# Overview_Schematic.net
KiCad netlist of a schematic drawn in EAGLE
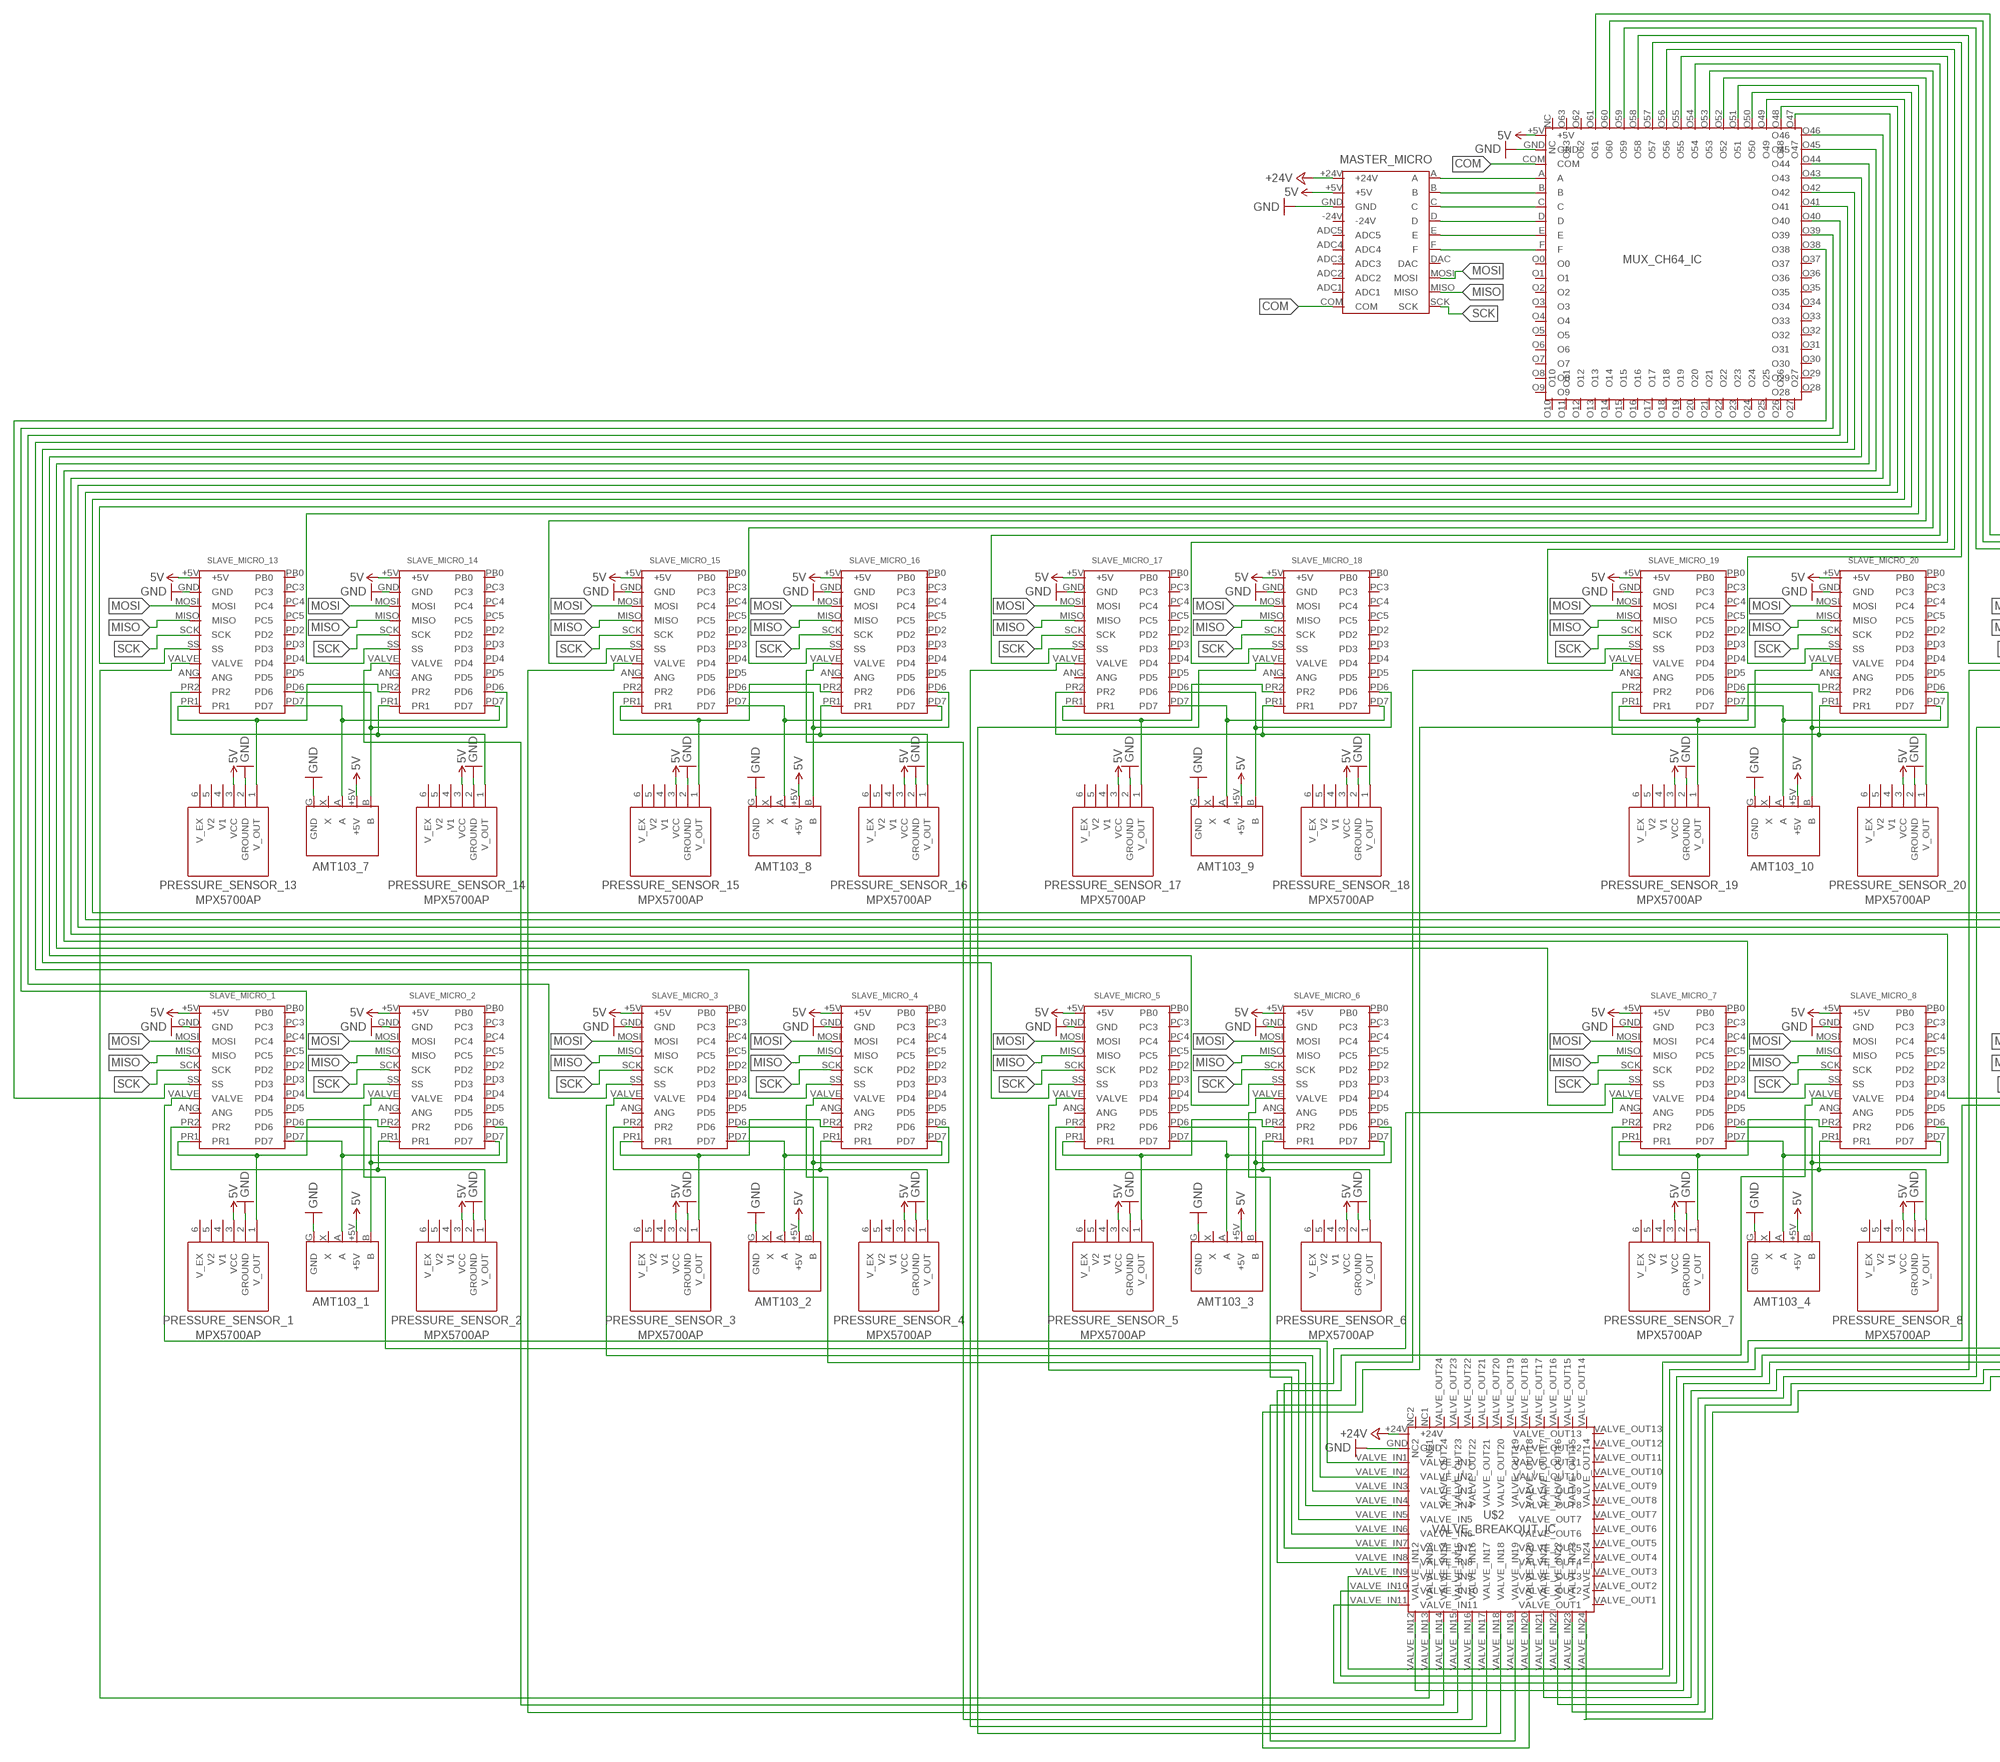
[diagram p0: schematic, sheet 1, part 1 of 2]
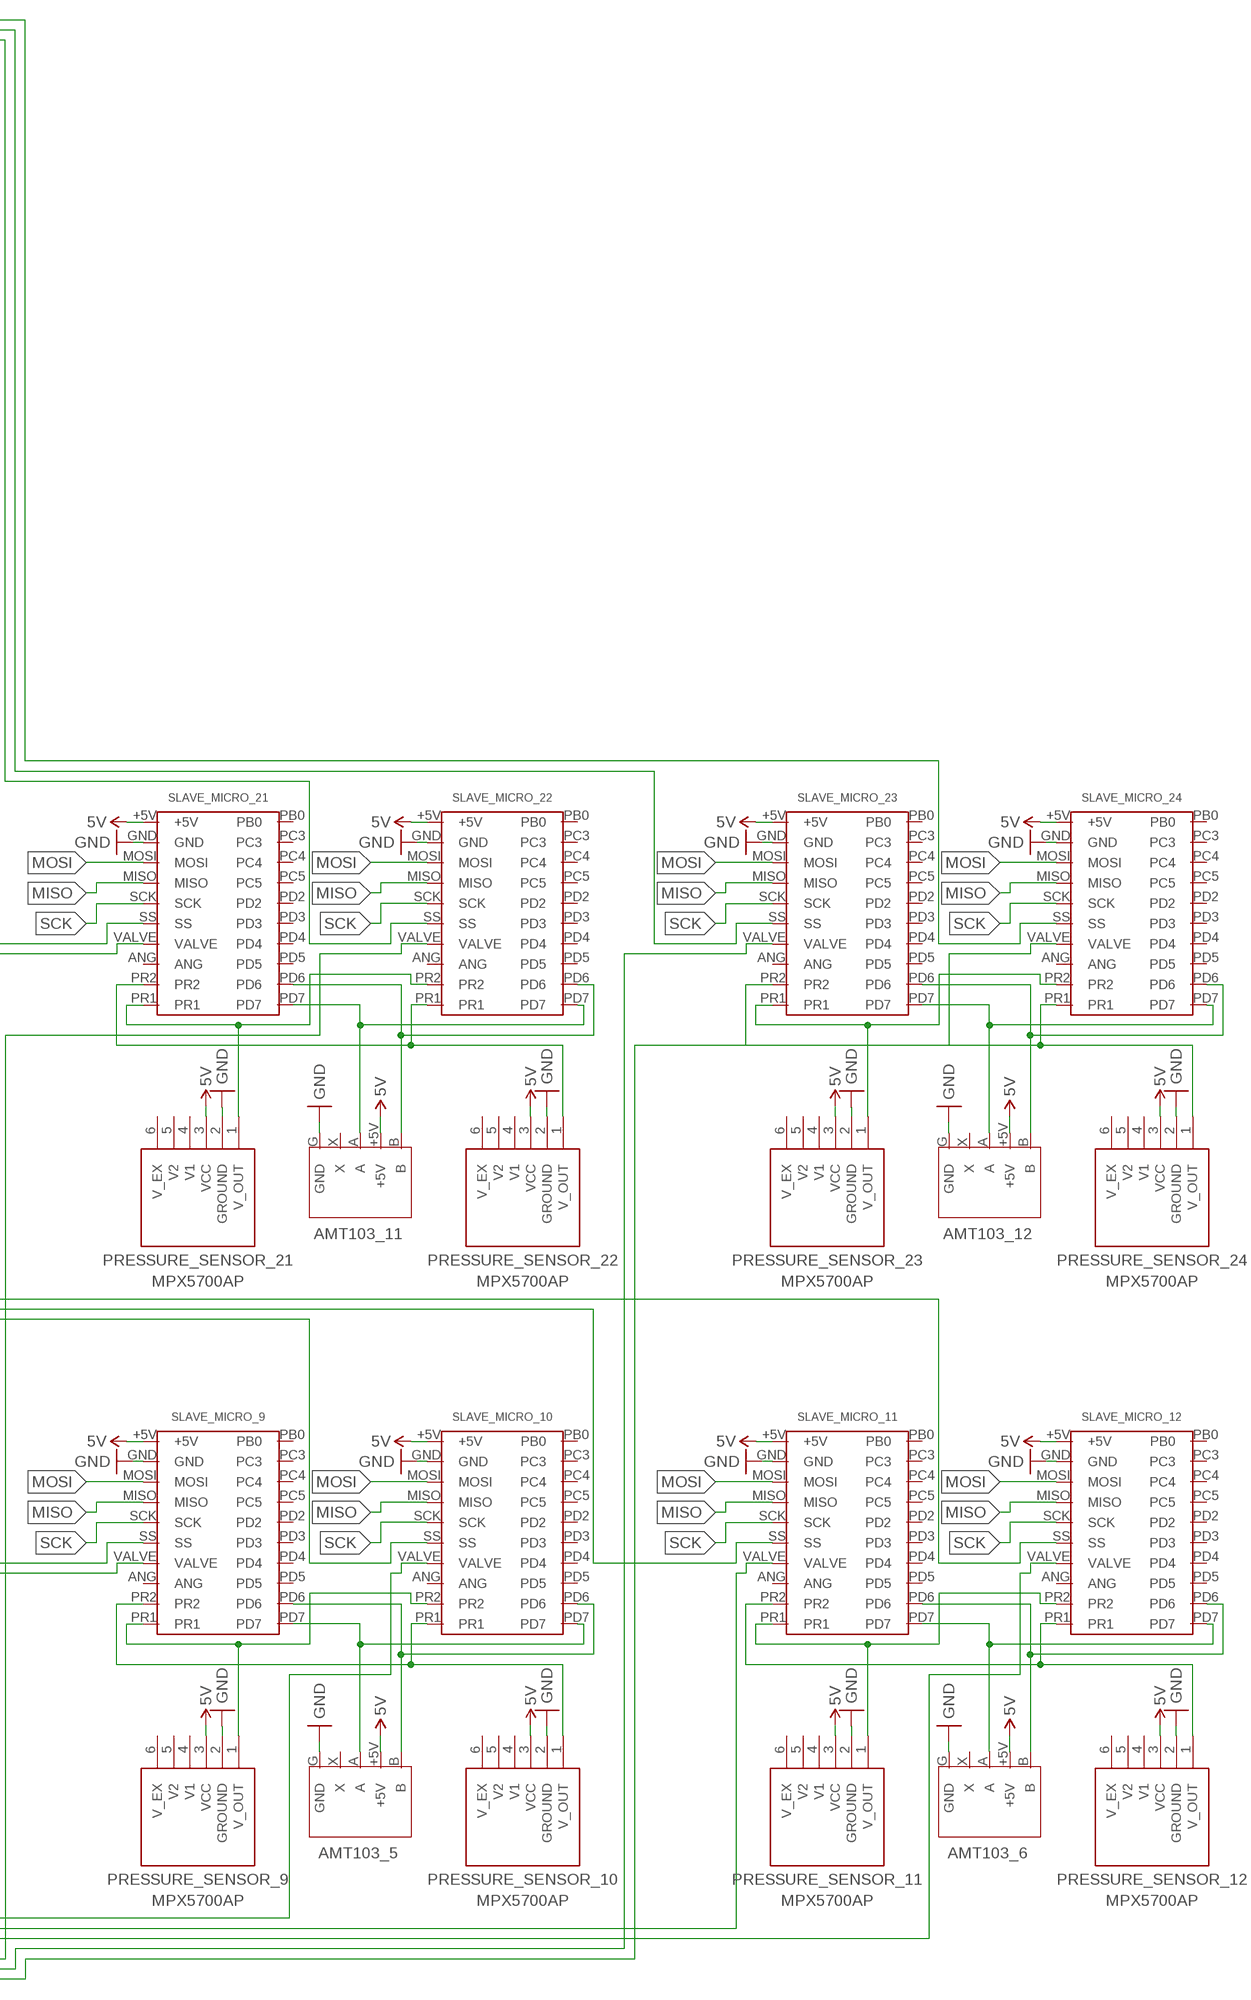
[diagram p1: schematic, sheet 1, part 2 of 2]

(export (version "E")
  (design (tool "Eeschema 10.0.6"))
  (components
    (comp (ref "AMT103_1")
      (value "AMT103_ENCODER")
      (footprint "eagle-import:AMT103_ENCODER")
      (libsource (lib "eagle-import") (part "AMT103_ENCODER"))
    )
    (comp (ref "AMT103_2")
      (value "AMT103_ENCODER")
      (footprint "eagle-import:AMT103_ENCODER")
      (libsource (lib "eagle-import") (part "AMT103_ENCODER"))
    )
    (comp (ref "AMT103_3")
      (value "AMT103_ENCODER")
      (footprint "eagle-import:AMT103_ENCODER")
      (libsource (lib "eagle-import") (part "AMT103_ENCODER"))
    )
    (comp (ref "AMT103_4")
      (value "AMT103_ENCODER")
      (footprint "eagle-import:AMT103_ENCODER")
      (libsource (lib "eagle-import") (part "AMT103_ENCODER"))
    )
    (comp (ref "AMT103_5")
      (value "AMT103_ENCODER")
      (footprint "eagle-import:AMT103_ENCODER")
      (libsource (lib "eagle-import") (part "AMT103_ENCODER"))
    )
    (comp (ref "AMT103_6")
      (value "AMT103_ENCODER")
      (footprint "eagle-import:AMT103_ENCODER")
      (libsource (lib "eagle-import") (part "AMT103_ENCODER"))
    )
    (comp (ref "AMT103_7")
      (value "AMT103_ENCODER")
      (footprint "eagle-import:AMT103_ENCODER")
      (libsource (lib "eagle-import") (part "AMT103_ENCODER"))
    )
    (comp (ref "AMT103_8")
      (value "AMT103_ENCODER")
      (footprint "eagle-import:AMT103_ENCODER")
      (libsource (lib "eagle-import") (part "AMT103_ENCODER"))
    )
    (comp (ref "AMT103_9")
      (value "AMT103_ENCODER")
      (footprint "eagle-import:AMT103_ENCODER")
      (libsource (lib "eagle-import") (part "AMT103_ENCODER"))
    )
    (comp (ref "AMT103_10")
      (value "AMT103_ENCODER")
      (footprint "eagle-import:AMT103_ENCODER")
      (libsource (lib "eagle-import") (part "AMT103_ENCODER"))
    )
    (comp (ref "AMT103_11")
      (value "AMT103_ENCODER")
      (footprint "eagle-import:AMT103_ENCODER")
      (libsource (lib "eagle-import") (part "AMT103_ENCODER"))
    )
    (comp (ref "AMT103_12")
      (value "AMT103_ENCODER")
      (footprint "eagle-import:AMT103_ENCODER")
      (libsource (lib "eagle-import") (part "AMT103_ENCODER"))
    )
    (comp (ref "MASTER_MICRO")
      (value "MASTER_MICRO")
      (footprint "eagle-import:MASTER_MICRO")
      (libsource (lib "eagle-import") (part "MASTER_MICRO"))
    )
    (comp (ref "MUX_CH64_IC")
      (value "MUX_64CH_IC")
      (footprint "eagle-import:MUX_64CH_IC")
      (libsource (lib "eagle-import") (part "MUX_64CH_IC"))
    )
    (comp (ref "PRESSURE_SENSOR_1")
      (value "MPX5700AP")
      (footprint "eagle-import:MPX5700AP")
      (fields (field (name "MOUSER_PART_NUMBER") "841-MPX5700AP"))
      (libsource (lib "eagle-import") (part "MPX5700AP"))
    )
    (comp (ref "PRESSURE_SENSOR_2")
      (value "MPX5700AP")
      (footprint "eagle-import:MPX5700AP")
      (fields (field (name "MOUSER_PART_NUMBER") "841-MPX5700AP"))
      (libsource (lib "eagle-import") (part "MPX5700AP"))
    )
    (comp (ref "PRESSURE_SENSOR_3")
      (value "MPX5700AP")
      (footprint "eagle-import:MPX5700AP")
      (fields (field (name "MOUSER_PART_NUMBER") "841-MPX5700AP"))
      (libsource (lib "eagle-import") (part "MPX5700AP"))
    )
    (comp (ref "PRESSURE_SENSOR_4")
      (value "MPX5700AP")
      (footprint "eagle-import:MPX5700AP")
      (fields (field (name "MOUSER_PART_NUMBER") "841-MPX5700AP"))
      (libsource (lib "eagle-import") (part "MPX5700AP"))
    )
    (comp (ref "PRESSURE_SENSOR_5")
      (value "MPX5700AP")
      (footprint "eagle-import:MPX5700AP")
      (fields (field (name "MOUSER_PART_NUMBER") "841-MPX5700AP"))
      (libsource (lib "eagle-import") (part "MPX5700AP"))
    )
    (comp (ref "PRESSURE_SENSOR_6")
      (value "MPX5700AP")
      (footprint "eagle-import:MPX5700AP")
      (fields (field (name "MOUSER_PART_NUMBER") "841-MPX5700AP"))
      (libsource (lib "eagle-import") (part "MPX5700AP"))
    )
    (comp (ref "PRESSURE_SENSOR_7")
      (value "MPX5700AP")
      (footprint "eagle-import:MPX5700AP")
      (fields (field (name "MOUSER_PART_NUMBER") "841-MPX5700AP"))
      (libsource (lib "eagle-import") (part "MPX5700AP"))
    )
    (comp (ref "PRESSURE_SENSOR_8")
      (value "MPX5700AP")
      (footprint "eagle-import:MPX5700AP")
      (fields (field (name "MOUSER_PART_NUMBER") "841-MPX5700AP"))
      (libsource (lib "eagle-import") (part "MPX5700AP"))
    )
    (comp (ref "PRESSURE_SENSOR_9")
      (value "MPX5700AP")
      (footprint "eagle-import:MPX5700AP")
      (fields (field (name "MOUSER_PART_NUMBER") "841-MPX5700AP"))
      (libsource (lib "eagle-import") (part "MPX5700AP"))
    )
    (comp (ref "PRESSURE_SENSOR_10")
      (value "MPX5700AP")
      (footprint "eagle-import:MPX5700AP")
      (fields (field (name "MOUSER_PART_NUMBER") "841-MPX5700AP"))
      (libsource (lib "eagle-import") (part "MPX5700AP"))
    )
    (comp (ref "PRESSURE_SENSOR_11")
      (value "MPX5700AP")
      (footprint "eagle-import:MPX5700AP")
      (fields (field (name "MOUSER_PART_NUMBER") "841-MPX5700AP"))
      (libsource (lib "eagle-import") (part "MPX5700AP"))
    )
    (comp (ref "PRESSURE_SENSOR_12")
      (value "MPX5700AP")
      (footprint "eagle-import:MPX5700AP")
      (fields (field (name "MOUSER_PART_NUMBER") "841-MPX5700AP"))
      (libsource (lib "eagle-import") (part "MPX5700AP"))
    )
    (comp (ref "PRESSURE_SENSOR_13")
      (value "MPX5700AP")
      (footprint "eagle-import:MPX5700AP")
      (fields (field (name "MOUSER_PART_NUMBER") "841-MPX5700AP"))
      (libsource (lib "eagle-import") (part "MPX5700AP"))
    )
    (comp (ref "PRESSURE_SENSOR_14")
      (value "MPX5700AP")
      (footprint "eagle-import:MPX5700AP")
      (fields (field (name "MOUSER_PART_NUMBER") "841-MPX5700AP"))
      (libsource (lib "eagle-import") (part "MPX5700AP"))
    )
    (comp (ref "PRESSURE_SENSOR_15")
      (value "MPX5700AP")
      (footprint "eagle-import:MPX5700AP")
      (fields (field (name "MOUSER_PART_NUMBER") "841-MPX5700AP"))
      (libsource (lib "eagle-import") (part "MPX5700AP"))
    )
    (comp (ref "PRESSURE_SENSOR_16")
      (value "MPX5700AP")
      (footprint "eagle-import:MPX5700AP")
      (fields (field (name "MOUSER_PART_NUMBER") "841-MPX5700AP"))
      (libsource (lib "eagle-import") (part "MPX5700AP"))
    )
    (comp (ref "PRESSURE_SENSOR_17")
      (value "MPX5700AP")
      (footprint "eagle-import:MPX5700AP")
      (fields (field (name "MOUSER_PART_NUMBER") "841-MPX5700AP"))
      (libsource (lib "eagle-import") (part "MPX5700AP"))
    )
    (comp (ref "PRESSURE_SENSOR_18")
      (value "MPX5700AP")
      (footprint "eagle-import:MPX5700AP")
      (fields (field (name "MOUSER_PART_NUMBER") "841-MPX5700AP"))
      (libsource (lib "eagle-import") (part "MPX5700AP"))
    )
    (comp (ref "PRESSURE_SENSOR_19")
      (value "MPX5700AP")
      (footprint "eagle-import:MPX5700AP")
      (fields (field (name "MOUSER_PART_NUMBER") "841-MPX5700AP"))
      (libsource (lib "eagle-import") (part "MPX5700AP"))
    )
    (comp (ref "PRESSURE_SENSOR_20")
      (value "MPX5700AP")
      (footprint "eagle-import:MPX5700AP")
      (fields (field (name "MOUSER_PART_NUMBER") "841-MPX5700AP"))
      (libsource (lib "eagle-import") (part "MPX5700AP"))
    )
    (comp (ref "PRESSURE_SENSOR_21")
      (value "MPX5700AP")
      (footprint "eagle-import:MPX5700AP")
      (fields (field (name "MOUSER_PART_NUMBER") "841-MPX5700AP"))
      (libsource (lib "eagle-import") (part "MPX5700AP"))
    )
    (comp (ref "PRESSURE_SENSOR_22")
      (value "MPX5700AP")
      (footprint "eagle-import:MPX5700AP")
      (fields (field (name "MOUSER_PART_NUMBER") "841-MPX5700AP"))
      (libsource (lib "eagle-import") (part "MPX5700AP"))
    )
    (comp (ref "PRESSURE_SENSOR_23")
      (value "MPX5700AP")
      (footprint "eagle-import:MPX5700AP")
      (fields (field (name "MOUSER_PART_NUMBER") "841-MPX5700AP"))
      (libsource (lib "eagle-import") (part "MPX5700AP"))
    )
    (comp (ref "PRESSURE_SENSOR_24")
      (value "MPX5700AP")
      (footprint "eagle-import:MPX5700AP")
      (fields (field (name "MOUSER_PART_NUMBER") "841-MPX5700AP"))
      (libsource (lib "eagle-import") (part "MPX5700AP"))
    )
    (comp (ref "SLAVE_MICRO_1")
      (value "SLAVE_MICRO")
      (footprint "eagle-import:SLAVE_MICRO")
      (libsource (lib "eagle-import") (part "SLAVE_MICRO"))
    )
    (comp (ref "SLAVE_MICRO_2")
      (value "SLAVE_MICRO")
      (footprint "eagle-import:SLAVE_MICRO")
      (libsource (lib "eagle-import") (part "SLAVE_MICRO"))
    )
    (comp (ref "SLAVE_MICRO_3")
      (value "SLAVE_MICRO")
      (footprint "eagle-import:SLAVE_MICRO")
      (libsource (lib "eagle-import") (part "SLAVE_MICRO"))
    )
    (comp (ref "SLAVE_MICRO_4")
      (value "SLAVE_MICRO")
      (footprint "eagle-import:SLAVE_MICRO")
      (libsource (lib "eagle-import") (part "SLAVE_MICRO"))
    )
    (comp (ref "SLAVE_MICRO_5")
      (value "SLAVE_MICRO")
      (footprint "eagle-import:SLAVE_MICRO")
      (libsource (lib "eagle-import") (part "SLAVE_MICRO"))
    )
    (comp (ref "SLAVE_MICRO_6")
      (value "SLAVE_MICRO")
      (footprint "eagle-import:SLAVE_MICRO")
      (libsource (lib "eagle-import") (part "SLAVE_MICRO"))
    )
    (comp (ref "SLAVE_MICRO_7")
      (value "SLAVE_MICRO")
      (footprint "eagle-import:SLAVE_MICRO")
      (libsource (lib "eagle-import") (part "SLAVE_MICRO"))
    )
    (comp (ref "SLAVE_MICRO_8")
      (value "SLAVE_MICRO")
      (footprint "eagle-import:SLAVE_MICRO")
      (libsource (lib "eagle-import") (part "SLAVE_MICRO"))
    )
    (comp (ref "SLAVE_MICRO_9")
      (value "SLAVE_MICRO")
      (footprint "eagle-import:SLAVE_MICRO")
      (libsource (lib "eagle-import") (part "SLAVE_MICRO"))
    )
    (comp (ref "SLAVE_MICRO_10")
      (value "SLAVE_MICRO")
      (footprint "eagle-import:SLAVE_MICRO")
      (libsource (lib "eagle-import") (part "SLAVE_MICRO"))
    )
    (comp (ref "SLAVE_MICRO_11")
      (value "SLAVE_MICRO")
      (footprint "eagle-import:SLAVE_MICRO")
      (libsource (lib "eagle-import") (part "SLAVE_MICRO"))
    )
    (comp (ref "SLAVE_MICRO_12")
      (value "SLAVE_MICRO")
      (footprint "eagle-import:SLAVE_MICRO")
      (libsource (lib "eagle-import") (part "SLAVE_MICRO"))
    )
    (comp (ref "SLAVE_MICRO_13")
      (value "SLAVE_MICRO")
      (footprint "eagle-import:SLAVE_MICRO")
      (libsource (lib "eagle-import") (part "SLAVE_MICRO"))
    )
    (comp (ref "SLAVE_MICRO_14")
      (value "SLAVE_MICRO")
      (footprint "eagle-import:SLAVE_MICRO")
      (libsource (lib "eagle-import") (part "SLAVE_MICRO"))
    )
    (comp (ref "SLAVE_MICRO_15")
      (value "SLAVE_MICRO")
      (footprint "eagle-import:SLAVE_MICRO")
      (libsource (lib "eagle-import") (part "SLAVE_MICRO"))
    )
    (comp (ref "SLAVE_MICRO_16")
      (value "SLAVE_MICRO")
      (footprint "eagle-import:SLAVE_MICRO")
      (libsource (lib "eagle-import") (part "SLAVE_MICRO"))
    )
    (comp (ref "SLAVE_MICRO_17")
      (value "SLAVE_MICRO")
      (footprint "eagle-import:SLAVE_MICRO")
      (libsource (lib "eagle-import") (part "SLAVE_MICRO"))
    )
    (comp (ref "SLAVE_MICRO_18")
      (value "SLAVE_MICRO")
      (footprint "eagle-import:SLAVE_MICRO")
      (libsource (lib "eagle-import") (part "SLAVE_MICRO"))
    )
    (comp (ref "SLAVE_MICRO_19")
      (value "SLAVE_MICRO")
      (footprint "eagle-import:SLAVE_MICRO")
      (libsource (lib "eagle-import") (part "SLAVE_MICRO"))
    )
    (comp (ref "SLAVE_MICRO_20")
      (value "SLAVE_MICRO")
      (footprint "eagle-import:SLAVE_MICRO")
      (libsource (lib "eagle-import") (part "SLAVE_MICRO"))
    )
    (comp (ref "SLAVE_MICRO_21")
      (value "SLAVE_MICRO")
      (footprint "eagle-import:SLAVE_MICRO")
      (libsource (lib "eagle-import") (part "SLAVE_MICRO"))
    )
    (comp (ref "SLAVE_MICRO_22")
      (value "SLAVE_MICRO")
      (footprint "eagle-import:SLAVE_MICRO")
      (libsource (lib "eagle-import") (part "SLAVE_MICRO"))
    )
    (comp (ref "SLAVE_MICRO_23")
      (value "SLAVE_MICRO")
      (footprint "eagle-import:SLAVE_MICRO")
      (libsource (lib "eagle-import") (part "SLAVE_MICRO"))
    )
    (comp (ref "SLAVE_MICRO_24")
      (value "SLAVE_MICRO")
      (footprint "eagle-import:SLAVE_MICRO")
      (libsource (lib "eagle-import") (part "SLAVE_MICRO"))
    )
    (comp (ref "U$2")
      (value "VALVE_BREAKOUT_IC")
      (footprint "eagle-import:VALVE_BREAKOUT_IC")
      (libsource (lib "eagle-import") (part "VALVE_BREAKOUT_IC"))
    )
  )
  (nets
    (net (code "1") (name "+24V") (class "Default")
      (node (ref "MASTER_MICRO") (pin "+24V") (pinfunction "+24V_+24V") (pintype "bidirectional"))
      (node (ref "U$2") (pin "+24V") (pinfunction "+24V_+24V") (pintype "bidirectional"))
    )
    (net (code "2") (name "5V") (class "Default")
      (node (ref "AMT103_1") (pin "+5V") (pinfunction "+5V_+5V") (pintype "bidirectional"))
      (node (ref "AMT103_10") (pin "+5V") (pinfunction "+5V_+5V") (pintype "bidirectional"))
      (node (ref "AMT103_11") (pin "+5V") (pinfunction "+5V_+5V") (pintype "bidirectional"))
      (node (ref "AMT103_12") (pin "+5V") (pinfunction "+5V_+5V") (pintype "bidirectional"))
      (node (ref "AMT103_2") (pin "+5V") (pinfunction "+5V_+5V") (pintype "bidirectional"))
      (node (ref "AMT103_3") (pin "+5V") (pinfunction "+5V_+5V") (pintype "bidirectional"))
      (node (ref "AMT103_4") (pin "+5V") (pinfunction "+5V_+5V") (pintype "bidirectional"))
      (node (ref "AMT103_5") (pin "+5V") (pinfunction "+5V_+5V") (pintype "bidirectional"))
      (node (ref "AMT103_6") (pin "+5V") (pinfunction "+5V_+5V") (pintype "bidirectional"))
      (node (ref "AMT103_7") (pin "+5V") (pinfunction "+5V_+5V") (pintype "bidirectional"))
      (node (ref "AMT103_8") (pin "+5V") (pinfunction "+5V_+5V") (pintype "bidirectional"))
      (node (ref "AMT103_9") (pin "+5V") (pinfunction "+5V_+5V") (pintype "bidirectional"))
      (node (ref "MASTER_MICRO") (pin "+5V") (pinfunction "+5V_+5V") (pintype "bidirectional"))
      (node (ref "MUX_CH64_IC") (pin "+5V") (pinfunction "+5V_+5V") (pintype "bidirectional"))
      (node (ref "PRESSURE_SENSOR_1") (pin "3") (pinfunction "VCC_3") (pintype "bidirectional"))
      (node (ref "PRESSURE_SENSOR_10") (pin "3") (pinfunction "VCC_3") (pintype "bidirectional"))
      (node (ref "PRESSURE_SENSOR_11") (pin "3") (pinfunction "VCC_3") (pintype "bidirectional"))
      (node (ref "PRESSURE_SENSOR_12") (pin "3") (pinfunction "VCC_3") (pintype "bidirectional"))
      (node (ref "PRESSURE_SENSOR_13") (pin "3") (pinfunction "VCC_3") (pintype "bidirectional"))
      (node (ref "PRESSURE_SENSOR_14") (pin "3") (pinfunction "VCC_3") (pintype "bidirectional"))
      (node (ref "PRESSURE_SENSOR_15") (pin "3") (pinfunction "VCC_3") (pintype "bidirectional"))
      (node (ref "PRESSURE_SENSOR_16") (pin "3") (pinfunction "VCC_3") (pintype "bidirectional"))
      (node (ref "PRESSURE_SENSOR_17") (pin "3") (pinfunction "VCC_3") (pintype "bidirectional"))
      (node (ref "PRESSURE_SENSOR_18") (pin "3") (pinfunction "VCC_3") (pintype "bidirectional"))
      (node (ref "PRESSURE_SENSOR_19") (pin "3") (pinfunction "VCC_3") (pintype "bidirectional"))
      (node (ref "PRESSURE_SENSOR_2") (pin "3") (pinfunction "VCC_3") (pintype "bidirectional"))
      (node (ref "PRESSURE_SENSOR_20") (pin "3") (pinfunction "VCC_3") (pintype "bidirectional"))
      (node (ref "PRESSURE_SENSOR_21") (pin "3") (pinfunction "VCC_3") (pintype "bidirectional"))
      (node (ref "PRESSURE_SENSOR_22") (pin "3") (pinfunction "VCC_3") (pintype "bidirectional"))
      (node (ref "PRESSURE_SENSOR_23") (pin "3") (pinfunction "VCC_3") (pintype "bidirectional"))
      (node (ref "PRESSURE_SENSOR_24") (pin "3") (pinfunction "VCC_3") (pintype "bidirectional"))
      (node (ref "PRESSURE_SENSOR_3") (pin "3") (pinfunction "VCC_3") (pintype "bidirectional"))
      (node (ref "PRESSURE_SENSOR_4") (pin "3") (pinfunction "VCC_3") (pintype "bidirectional"))
      (node (ref "PRESSURE_SENSOR_5") (pin "3") (pinfunction "VCC_3") (pintype "bidirectional"))
      (node (ref "PRESSURE_SENSOR_6") (pin "3") (pinfunction "VCC_3") (pintype "bidirectional"))
      (node (ref "PRESSURE_SENSOR_7") (pin "3") (pinfunction "VCC_3") (pintype "bidirectional"))
      (node (ref "PRESSURE_SENSOR_8") (pin "3") (pinfunction "VCC_3") (pintype "bidirectional"))
      (node (ref "PRESSURE_SENSOR_9") (pin "3") (pinfunction "VCC_3") (pintype "bidirectional"))
      (node (ref "SLAVE_MICRO_1") (pin "+5V") (pinfunction "+5V_+5V") (pintype "bidirectional"))
      (node (ref "SLAVE_MICRO_10") (pin "+5V") (pinfunction "+5V_+5V") (pintype "bidirectional"))
      (node (ref "SLAVE_MICRO_11") (pin "+5V") (pinfunction "+5V_+5V") (pintype "bidirectional"))
      (node (ref "SLAVE_MICRO_12") (pin "+5V") (pinfunction "+5V_+5V") (pintype "bidirectional"))
      (node (ref "SLAVE_MICRO_13") (pin "+5V") (pinfunction "+5V_+5V") (pintype "bidirectional"))
      (node (ref "SLAVE_MICRO_14") (pin "+5V") (pinfunction "+5V_+5V") (pintype "bidirectional"))
      (node (ref "SLAVE_MICRO_15") (pin "+5V") (pinfunction "+5V_+5V") (pintype "bidirectional"))
      (node (ref "SLAVE_MICRO_16") (pin "+5V") (pinfunction "+5V_+5V") (pintype "bidirectional"))
      (node (ref "SLAVE_MICRO_17") (pin "+5V") (pinfunction "+5V_+5V") (pintype "bidirectional"))
      (node (ref "SLAVE_MICRO_18") (pin "+5V") (pinfunction "+5V_+5V") (pintype "bidirectional"))
      (node (ref "SLAVE_MICRO_19") (pin "+5V") (pinfunction "+5V_+5V") (pintype "bidirectional"))
      (node (ref "SLAVE_MICRO_2") (pin "+5V") (pinfunction "+5V_+5V") (pintype "bidirectional"))
      (node (ref "SLAVE_MICRO_20") (pin "+5V") (pinfunction "+5V_+5V") (pintype "bidirectional"))
      (node (ref "SLAVE_MICRO_21") (pin "+5V") (pinfunction "+5V_+5V") (pintype "bidirectional"))
      (node (ref "SLAVE_MICRO_22") (pin "+5V") (pinfunction "+5V_+5V") (pintype "bidirectional"))
      (node (ref "SLAVE_MICRO_23") (pin "+5V") (pinfunction "+5V_+5V") (pintype "bidirectional"))
      (node (ref "SLAVE_MICRO_24") (pin "+5V") (pinfunction "+5V_+5V") (pintype "bidirectional"))
      (node (ref "SLAVE_MICRO_3") (pin "+5V") (pinfunction "+5V_+5V") (pintype "bidirectional"))
      (node (ref "SLAVE_MICRO_4") (pin "+5V") (pinfunction "+5V_+5V") (pintype "bidirectional"))
      (node (ref "SLAVE_MICRO_5") (pin "+5V") (pinfunction "+5V_+5V") (pintype "bidirectional"))
      (node (ref "SLAVE_MICRO_6") (pin "+5V") (pinfunction "+5V_+5V") (pintype "bidirectional"))
      (node (ref "SLAVE_MICRO_7") (pin "+5V") (pinfunction "+5V_+5V") (pintype "bidirectional"))
      (node (ref "SLAVE_MICRO_8") (pin "+5V") (pinfunction "+5V_+5V") (pintype "bidirectional"))
      (node (ref "SLAVE_MICRO_9") (pin "+5V") (pinfunction "+5V_+5V") (pintype "bidirectional"))
    )
    (net (code "3") (name "COM") (class "Default")
      (node (ref "MASTER_MICRO") (pin "COM") (pinfunction "COM_COM") (pintype "bidirectional"))
      (node (ref "MUX_CH64_IC") (pin "COM") (pinfunction "COM_COM") (pintype "bidirectional"))
    )
    (net (code "4") (name "GND") (class "Default")
      (node (ref "AMT103_1") (pin "G") (pinfunction "GND_G") (pintype "bidirectional"))
      (node (ref "AMT103_10") (pin "G") (pinfunction "GND_G") (pintype "bidirectional"))
      (node (ref "AMT103_11") (pin "G") (pinfunction "GND_G") (pintype "bidirectional"))
      (node (ref "AMT103_12") (pin "G") (pinfunction "GND_G") (pintype "bidirectional"))
      (node (ref "AMT103_2") (pin "G") (pinfunction "GND_G") (pintype "bidirectional"))
      (node (ref "AMT103_3") (pin "G") (pinfunction "GND_G") (pintype "bidirectional"))
      (node (ref "AMT103_4") (pin "G") (pinfunction "GND_G") (pintype "bidirectional"))
      (node (ref "AMT103_5") (pin "G") (pinfunction "GND_G") (pintype "bidirectional"))
      (node (ref "AMT103_6") (pin "G") (pinfunction "GND_G") (pintype "bidirectional"))
      (node (ref "AMT103_7") (pin "G") (pinfunction "GND_G") (pintype "bidirectional"))
      (node (ref "AMT103_8") (pin "G") (pinfunction "GND_G") (pintype "bidirectional"))
      (node (ref "AMT103_9") (pin "G") (pinfunction "GND_G") (pintype "bidirectional"))
      (node (ref "MASTER_MICRO") (pin "GND") (pinfunction "GND_GND") (pintype "bidirectional"))
      (node (ref "MUX_CH64_IC") (pin "GND") (pinfunction "GND_GND") (pintype "bidirectional"))
      (node (ref "PRESSURE_SENSOR_1") (pin "2") (pinfunction "GROUND_2") (pintype "bidirectional"))
      (node (ref "PRESSURE_SENSOR_10") (pin "2") (pinfunction "GROUND_2") (pintype "bidirectional"))
      (node (ref "PRESSURE_SENSOR_11") (pin "2") (pinfunction "GROUND_2") (pintype "bidirectional"))
      (node (ref "PRESSURE_SENSOR_12") (pin "2") (pinfunction "GROUND_2") (pintype "bidirectional"))
      (node (ref "PRESSURE_SENSOR_13") (pin "2") (pinfunction "GROUND_2") (pintype "bidirectional"))
      (node (ref "PRESSURE_SENSOR_14") (pin "2") (pinfunction "GROUND_2") (pintype "bidirectional"))
      (node (ref "PRESSURE_SENSOR_15") (pin "2") (pinfunction "GROUND_2") (pintype "bidirectional"))
      (node (ref "PRESSURE_SENSOR_16") (pin "2") (pinfunction "GROUND_2") (pintype "bidirectional"))
      (node (ref "PRESSURE_SENSOR_17") (pin "2") (pinfunction "GROUND_2") (pintype "bidirectional"))
      (node (ref "PRESSURE_SENSOR_18") (pin "2") (pinfunction "GROUND_2") (pintype "bidirectional"))
      (node (ref "PRESSURE_SENSOR_19") (pin "2") (pinfunction "GROUND_2") (pintype "bidirectional"))
      (node (ref "PRESSURE_SENSOR_2") (pin "2") (pinfunction "GROUND_2") (pintype "bidirectional"))
      (node (ref "PRESSURE_SENSOR_20") (pin "2") (pinfunction "GROUND_2") (pintype "bidirectional"))
      (node (ref "PRESSURE_SENSOR_21") (pin "2") (pinfunction "GROUND_2") (pintype "bidirectional"))
      (node (ref "PRESSURE_SENSOR_22") (pin "2") (pinfunction "GROUND_2") (pintype "bidirectional"))
      (node (ref "PRESSURE_SENSOR_23") (pin "2") (pinfunction "GROUND_2") (pintype "bidirectional"))
      (node (ref "PRESSURE_SENSOR_24") (pin "2") (pinfunction "GROUND_2") (pintype "bidirectional"))
      (node (ref "PRESSURE_SENSOR_3") (pin "2") (pinfunction "GROUND_2") (pintype "bidirectional"))
      (node (ref "PRESSURE_SENSOR_4") (pin "2") (pinfunction "GROUND_2") (pintype "bidirectional"))
      (node (ref "PRESSURE_SENSOR_5") (pin "2") (pinfunction "GROUND_2") (pintype "bidirectional"))
      (node (ref "PRESSURE_SENSOR_6") (pin "2") (pinfunction "GROUND_2") (pintype "bidirectional"))
      (node (ref "PRESSURE_SENSOR_7") (pin "2") (pinfunction "GROUND_2") (pintype "bidirectional"))
      (node (ref "PRESSURE_SENSOR_8") (pin "2") (pinfunction "GROUND_2") (pintype "bidirectional"))
      (node (ref "PRESSURE_SENSOR_9") (pin "2") (pinfunction "GROUND_2") (pintype "bidirectional"))
      (node (ref "SLAVE_MICRO_1") (pin "GND") (pinfunction "GND_GND") (pintype "bidirectional"))
      (node (ref "SLAVE_MICRO_10") (pin "GND") (pinfunction "GND_GND") (pintype "bidirectional"))
      (node (ref "SLAVE_MICRO_11") (pin "GND") (pinfunction "GND_GND") (pintype "bidirectional"))
      (node (ref "SLAVE_MICRO_12") (pin "GND") (pinfunction "GND_GND") (pintype "bidirectional"))
      (node (ref "SLAVE_MICRO_13") (pin "GND") (pinfunction "GND_GND") (pintype "bidirectional"))
      (node (ref "SLAVE_MICRO_14") (pin "GND") (pinfunction "GND_GND") (pintype "bidirectional"))
      (node (ref "SLAVE_MICRO_15") (pin "GND") (pinfunction "GND_GND") (pintype "bidirectional"))
      (node (ref "SLAVE_MICRO_16") (pin "GND") (pinfunction "GND_GND") (pintype "bidirectional"))
      (node (ref "SLAVE_MICRO_17") (pin "GND") (pinfunction "GND_GND") (pintype "bidirectional"))
      (node (ref "SLAVE_MICRO_18") (pin "GND") (pinfunction "GND_GND") (pintype "bidirectional"))
      (node (ref "SLAVE_MICRO_19") (pin "GND") (pinfunction "GND_GND") (pintype "bidirectional"))
      (node (ref "SLAVE_MICRO_2") (pin "GND") (pinfunction "GND_GND") (pintype "bidirectional"))
      (node (ref "SLAVE_MICRO_20") (pin "GND") (pinfunction "GND_GND") (pintype "bidirectional"))
      (node (ref "SLAVE_MICRO_21") (pin "GND") (pinfunction "GND_GND") (pintype "bidirectional"))
      (node (ref "SLAVE_MICRO_22") (pin "GND") (pinfunction "GND_GND") (pintype "bidirectional"))
      (node (ref "SLAVE_MICRO_23") (pin "GND") (pinfunction "GND_GND") (pintype "bidirectional"))
      (node (ref "SLAVE_MICRO_24") (pin "GND") (pinfunction "GND_GND") (pintype "bidirectional"))
      (node (ref "SLAVE_MICRO_3") (pin "GND") (pinfunction "GND_GND") (pintype "bidirectional"))
      (node (ref "SLAVE_MICRO_4") (pin "GND") (pinfunction "GND_GND") (pintype "bidirectional"))
      (node (ref "SLAVE_MICRO_5") (pin "GND") (pinfunction "GND_GND") (pintype "bidirectional"))
      (node (ref "SLAVE_MICRO_6") (pin "GND") (pinfunction "GND_GND") (pintype "bidirectional"))
      (node (ref "SLAVE_MICRO_7") (pin "GND") (pinfunction "GND_GND") (pintype "bidirectional"))
      (node (ref "SLAVE_MICRO_8") (pin "GND") (pinfunction "GND_GND") (pintype "bidirectional"))
      (node (ref "SLAVE_MICRO_9") (pin "GND") (pinfunction "GND_GND") (pintype "bidirectional"))
      (node (ref "U$2") (pin "GND") (pinfunction "GND_GND") (pintype "bidirectional"))
    )
    (net (code "5") (name "MISO") (class "Default")
      (node (ref "MASTER_MICRO") (pin "MISO") (pinfunction "MISO_MISO") (pintype "bidirectional"))
      (node (ref "SLAVE_MICRO_1") (pin "MISO") (pinfunction "MISO_MISO") (pintype "bidirectional"))
      (node (ref "SLAVE_MICRO_10") (pin "MISO") (pinfunction "MISO_MISO") (pintype "bidirectional"))
      (node (ref "SLAVE_MICRO_11") (pin "MISO") (pinfunction "MISO_MISO") (pintype "bidirectional"))
      (node (ref "SLAVE_MICRO_12") (pin "MISO") (pinfunction "MISO_MISO") (pintype "bidirectional"))
      (node (ref "SLAVE_MICRO_13") (pin "MISO") (pinfunction "MISO_MISO") (pintype "bidirectional"))
      (node (ref "SLAVE_MICRO_14") (pin "MISO") (pinfunction "MISO_MISO") (pintype "bidirectional"))
      (node (ref "SLAVE_MICRO_15") (pin "MISO") (pinfunction "MISO_MISO") (pintype "bidirectional"))
      (node (ref "SLAVE_MICRO_16") (pin "MISO") (pinfunction "MISO_MISO") (pintype "bidirectional"))
      (node (ref "SLAVE_MICRO_17") (pin "MISO") (pinfunction "MISO_MISO") (pintype "bidirectional"))
      (node (ref "SLAVE_MICRO_18") (pin "MISO") (pinfunction "MISO_MISO") (pintype "bidirectional"))
      (node (ref "SLAVE_MICRO_19") (pin "MISO") (pinfunction "MISO_MISO") (pintype "bidirectional"))
      (node (ref "SLAVE_MICRO_2") (pin "MISO") (pinfunction "MISO_MISO") (pintype "bidirectional"))
      (node (ref "SLAVE_MICRO_20") (pin "MISO") (pinfunction "MISO_MISO") (pintype "bidirectional"))
      (node (ref "SLAVE_MICRO_21") (pin "MISO") (pinfunction "MISO_MISO") (pintype "bidirectional"))
      (node (ref "SLAVE_MICRO_22") (pin "MISO") (pinfunction "MISO_MISO") (pintype "bidirectional"))
      (node (ref "SLAVE_MICRO_23") (pin "MISO") (pinfunction "MISO_MISO") (pintype "bidirectional"))
      (node (ref "SLAVE_MICRO_24") (pin "MISO") (pinfunction "MISO_MISO") (pintype "bidirectional"))
      (node (ref "SLAVE_MICRO_3") (pin "MISO") (pinfunction "MISO_MISO") (pintype "bidirectional"))
      (node (ref "SLAVE_MICRO_4") (pin "MISO") (pinfunction "MISO_MISO") (pintype "bidirectional"))
      (node (ref "SLAVE_MICRO_5") (pin "MISO") (pinfunction "MISO_MISO") (pintype "bidirectional"))
      (node (ref "SLAVE_MICRO_6") (pin "MISO") (pinfunction "MISO_MISO") (pintype "bidirectional"))
      (node (ref "SLAVE_MICRO_7") (pin "MISO") (pinfunction "MISO_MISO") (pintype "bidirectional"))
      (node (ref "SLAVE_MICRO_8") (pin "MISO") (pinfunction "MISO_MISO") (pintype "bidirectional"))
      (node (ref "SLAVE_MICRO_9") (pin "MISO") (pinfunction "MISO_MISO") (pintype "bidirectional"))
    )
    (net (code "6") (name "MOSI") (class "Default")
      (node (ref "MASTER_MICRO") (pin "MOSI") (pinfunction "MOSI_MOSI") (pintype "bidirectional"))
      (node (ref "SLAVE_MICRO_1") (pin "MOSI") (pinfunction "MOSI_MOSI") (pintype "bidirectional"))
      (node (ref "SLAVE_MICRO_10") (pin "MOSI") (pinfunction "MOSI_MOSI") (pintype "bidirectional"))
      (node (ref "SLAVE_MICRO_11") (pin "MOSI") (pinfunction "MOSI_MOSI") (pintype "bidirectional"))
      (node (ref "SLAVE_MICRO_12") (pin "MOSI") (pinfunction "MOSI_MOSI") (pintype "bidirectional"))
      (node (ref "SLAVE_MICRO_13") (pin "MOSI") (pinfunction "MOSI_MOSI") (pintype "bidirectional"))
      (node (ref "SLAVE_MICRO_14") (pin "MOSI") (pinfunction "MOSI_MOSI") (pintype "bidirectional"))
      (node (ref "SLAVE_MICRO_15") (pin "MOSI") (pinfunction "MOSI_MOSI") (pintype "bidirectional"))
      (node (ref "SLAVE_MICRO_16") (pin "MOSI") (pinfunction "MOSI_MOSI") (pintype "bidirectional"))
      (node (ref "SLAVE_MICRO_17") (pin "MOSI") (pinfunction "MOSI_MOSI") (pintype "bidirectional"))
      (node (ref "SLAVE_MICRO_18") (pin "MOSI") (pinfunction "MOSI_MOSI") (pintype "bidirectional"))
      (node (ref "SLAVE_MICRO_19") (pin "MOSI") (pinfunction "MOSI_MOSI") (pintype "bidirectional"))
      (node (ref "SLAVE_MICRO_2") (pin "MOSI") (pinfunction "MOSI_MOSI") (pintype "bidirectional"))
      (node (ref "SLAVE_MICRO_20") (pin "MOSI") (pinfunction "MOSI_MOSI") (pintype "bidirectional"))
      (node (ref "SLAVE_MICRO_21") (pin "MOSI") (pinfunction "MOSI_MOSI") (pintype "bidirectional"))
      (node (ref "SLAVE_MICRO_22") (pin "MOSI") (pinfunction "MOSI_MOSI") (pintype "bidirectional"))
      (node (ref "SLAVE_MICRO_23") (pin "MOSI") (pinfunction "MOSI_MOSI") (pintype "bidirectional"))
      (node (ref "SLAVE_MICRO_24") (pin "MOSI") (pinfunction "MOSI_MOSI") (pintype "bidirectional"))
      (node (ref "SLAVE_MICRO_3") (pin "MOSI") (pinfunction "MOSI_MOSI") (pintype "bidirectional"))
      (node (ref "SLAVE_MICRO_4") (pin "MOSI") (pinfunction "MOSI_MOSI") (pintype "bidirectional"))
      (node (ref "SLAVE_MICRO_5") (pin "MOSI") (pinfunction "MOSI_MOSI") (pintype "bidirectional"))
      (node (ref "SLAVE_MICRO_6") (pin "MOSI") (pinfunction "MOSI_MOSI") (pintype "bidirectional"))
      (node (ref "SLAVE_MICRO_7") (pin "MOSI") (pinfunction "MOSI_MOSI") (pintype "bidirectional"))
      (node (ref "SLAVE_MICRO_8") (pin "MOSI") (pinfunction "MOSI_MOSI") (pintype "bidirectional"))
      (node (ref "SLAVE_MICRO_9") (pin "MOSI") (pinfunction "MOSI_MOSI") (pintype "bidirectional"))
    )
    (net (code "7") (name "Net-(AMT103_1-PadA)") (class "Default")
      (node (ref "AMT103_1") (pin "A") (pinfunction "A_A") (pintype "bidirectional"))
      (node (ref "SLAVE_MICRO_1") (pin "PD7") (pinfunction "PD7_PD7") (pintype "bidirectional"))
      (node (ref "SLAVE_MICRO_2") (pin "PD7") (pinfunction "PD7_PD7") (pintype "bidirectional"))
    )
    (net (code "8") (name "Net-(AMT103_1-PadB)") (class "Default")
      (node (ref "AMT103_1") (pin "B") (pinfunction "B_B") (pintype "bidirectional"))
      (node (ref "SLAVE_MICRO_1") (pin "PD6") (pinfunction "PD6_PD6") (pintype "bidirectional"))
      (node (ref "SLAVE_MICRO_2") (pin "PD6") (pinfunction "PD6_PD6") (pintype "bidirectional"))
    )
    (net (code "9") (name "Net-(AMT103_2-PadA)") (class "Default")
      (node (ref "AMT103_2") (pin "A") (pinfunction "A_A") (pintype "bidirectional"))
      (node (ref "SLAVE_MICRO_3") (pin "PD7") (pinfunction "PD7_PD7") (pintype "bidirectional"))
      (node (ref "SLAVE_MICRO_4") (pin "PD7") (pinfunction "PD7_PD7") (pintype "bidirectional"))
    )
    (net (code "10") (name "Net-(AMT103_2-PadB)") (class "Default")
      (node (ref "AMT103_2") (pin "B") (pinfunction "B_B") (pintype "bidirectional"))
      (node (ref "SLAVE_MICRO_3") (pin "PD6") (pinfunction "PD6_PD6") (pintype "bidirectional"))
      (node (ref "SLAVE_MICRO_4") (pin "PD6") (pinfunction "PD6_PD6") (pintype "bidirectional"))
    )
    (net (code "11") (name "Net-(AMT103_3-PadA)") (class "Default")
      (node (ref "AMT103_3") (pin "A") (pinfunction "A_A") (pintype "bidirectional"))
      (node (ref "SLAVE_MICRO_5") (pin "PD7") (pinfunction "PD7_PD7") (pintype "bidirectional"))
      (node (ref "SLAVE_MICRO_6") (pin "PD7") (pinfunction "PD7_PD7") (pintype "bidirectional"))
    )
    (net (code "12") (name "Net-(AMT103_3-PadB)") (class "Default")
      (node (ref "AMT103_3") (pin "B") (pinfunction "B_B") (pintype "bidirectional"))
      (node (ref "SLAVE_MICRO_5") (pin "PD6") (pinfunction "PD6_PD6") (pintype "bidirectional"))
      (node (ref "SLAVE_MICRO_6") (pin "PD6") (pinfunction "PD6_PD6") (pintype "bidirectional"))
    )
    (net (code "13") (name "Net-(AMT103_4-PadA)") (class "Default")
      (node (ref "AMT103_4") (pin "A") (pinfunction "A_A") (pintype "bidirectional"))
      (node (ref "SLAVE_MICRO_7") (pin "PD7") (pinfunction "PD7_PD7") (pintype "bidirectional"))
      (node (ref "SLAVE_MICRO_8") (pin "PD7") (pinfunction "PD7_PD7") (pintype "bidirectional"))
    )
    (net (code "14") (name "Net-(AMT103_4-PadB)") (class "Default")
      (node (ref "AMT103_4") (pin "B") (pinfunction "B_B") (pintype "bidirectional"))
      (node (ref "SLAVE_MICRO_7") (pin "PD6") (pinfunction "PD6_PD6") (pintype "bidirectional"))
      (node (ref "SLAVE_MICRO_8") (pin "PD6") (pinfunction "PD6_PD6") (pintype "bidirectional"))
    )
    (net (code "15") (name "Net-(AMT103_5-PadA)") (class "Default")
      (node (ref "AMT103_5") (pin "A") (pinfunction "A_A") (pintype "bidirectional"))
      (node (ref "SLAVE_MICRO_10") (pin "PD7") (pinfunction "PD7_PD7") (pintype "bidirectional"))
      (node (ref "SLAVE_MICRO_9") (pin "PD7") (pinfunction "PD7_PD7") (pintype "bidirectional"))
    )
    (net (code "16") (name "Net-(AMT103_5-PadB)") (class "Default")
      (node (ref "AMT103_5") (pin "B") (pinfunction "B_B") (pintype "bidirectional"))
      (node (ref "SLAVE_MICRO_10") (pin "PD6") (pinfunction "PD6_PD6") (pintype "bidirectional"))
      (node (ref "SLAVE_MICRO_9") (pin "PD6") (pinfunction "PD6_PD6") (pintype "bidirectional"))
    )
    (net (code "17") (name "Net-(AMT103_6-PadA)") (class "Default")
      (node (ref "AMT103_6") (pin "A") (pinfunction "A_A") (pintype "bidirectional"))
      (node (ref "SLAVE_MICRO_11") (pin "PD7") (pinfunction "PD7_PD7") (pintype "bidirectional"))
      (node (ref "SLAVE_MICRO_12") (pin "PD7") (pinfunction "PD7_PD7") (pintype "bidirectional"))
    )
    (net (code "18") (name "Net-(AMT103_6-PadB)") (class "Default")
      (node (ref "AMT103_6") (pin "B") (pinfunction "B_B") (pintype "bidirectional"))
      (node (ref "SLAVE_MICRO_11") (pin "PD6") (pinfunction "PD6_PD6") (pintype "bidirectional"))
      (node (ref "SLAVE_MICRO_12") (pin "PD6") (pinfunction "PD6_PD6") (pintype "bidirectional"))
    )
    (net (code "19") (name "Net-(AMT103_7-PadA)") (class "Default")
      (node (ref "AMT103_7") (pin "A") (pinfunction "A_A") (pintype "bidirectional"))
      (node (ref "SLAVE_MICRO_13") (pin "PD7") (pinfunction "PD7_PD7") (pintype "bidirectional"))
      (node (ref "SLAVE_MICRO_14") (pin "PD7") (pinfunction "PD7_PD7") (pintype "bidirectional"))
    )
    (net (code "20") (name "Net-(AMT103_7-PadB)") (class "Default")
      (node (ref "AMT103_7") (pin "B") (pinfunction "B_B") (pintype "bidirectional"))
      (node (ref "SLAVE_MICRO_13") (pin "PD6") (pinfunction "PD6_PD6") (pintype "bidirectional"))
      (node (ref "SLAVE_MICRO_14") (pin "PD6") (pinfunction "PD6_PD6") (pintype "bidirectional"))
    )
    (net (code "21") (name "Net-(AMT103_8-PadA)") (class "Default")
      (node (ref "AMT103_8") (pin "A") (pinfunction "A_A") (pintype "bidirectional"))
      (node (ref "SLAVE_MICRO_15") (pin "PD7") (pinfunction "PD7_PD7") (pintype "bidirectional"))
      (node (ref "SLAVE_MICRO_16") (pin "PD7") (pinfunction "PD7_PD7") (pintype "bidirectional"))
    )
    (net (code "22") (name "Net-(AMT103_8-PadB)") (class "Default")
      (node (ref "AMT103_8") (pin "B") (pinfunction "B_B") (pintype "bidirectional"))
      (node (ref "SLAVE_MICRO_15") (pin "PD6") (pinfunction "PD6_PD6") (pintype "bidirectional"))
      (node (ref "SLAVE_MICRO_16") (pin "PD6") (pinfunction "PD6_PD6") (pintype "bidirectional"))
    )
    (net (code "23") (name "Net-(AMT103_9-PadA)") (class "Default")
      (node (ref "AMT103_9") (pin "A") (pinfunction "A_A") (pintype "bidirectional"))
      (node (ref "SLAVE_MICRO_17") (pin "PD7") (pinfunction "PD7_PD7") (pintype "bidirectional"))
      (node (ref "SLAVE_MICRO_18") (pin "PD7") (pinfunction "PD7_PD7") (pintype "bidirectional"))
    )
    (net (code "24") (name "Net-(AMT103_9-PadB)") (class "Default")
      (node (ref "AMT103_9") (pin "B") (pinfunction "B_B") (pintype "bidirectional"))
      (node (ref "SLAVE_MICRO_17") (pin "PD6") (pinfunction "PD6_PD6") (pintype "bidirectional"))
      (node (ref "SLAVE_MICRO_18") (pin "PD6") (pinfunction "PD6_PD6") (pintype "bidirectional"))
    )
    (net (code "25") (name "Net-(AMT103_10-PadA)") (class "Default")
      (node (ref "AMT103_10") (pin "A") (pinfunction "A_A") (pintype "bidirectional"))
      (node (ref "SLAVE_MICRO_19") (pin "PD7") (pinfunction "PD7_PD7") (pintype "bidirectional"))
      (node (ref "SLAVE_MICRO_20") (pin "PD7") (pinfunction "PD7_PD7") (pintype "bidirectional"))
    )
    (net (code "26") (name "Net-(AMT103_10-PadB)") (class "Default")
      (node (ref "AMT103_10") (pin "B") (pinfunction "B_B") (pintype "bidirectional"))
      (node (ref "SLAVE_MICRO_19") (pin "PD6") (pinfunction "PD6_PD6") (pintype "bidirectional"))
      (node (ref "SLAVE_MICRO_20") (pin "PD6") (pinfunction "PD6_PD6") (pintype "bidirectional"))
    )
    (net (code "27") (name "Net-(AMT103_11-PadA)") (class "Default")
      (node (ref "AMT103_11") (pin "A") (pinfunction "A_A") (pintype "bidirectional"))
      (node (ref "SLAVE_MICRO_21") (pin "PD7") (pinfunction "PD7_PD7") (pintype "bidirectional"))
      (node (ref "SLAVE_MICRO_22") (pin "PD7") (pinfunction "PD7_PD7") (pintype "bidirectional"))
    )
    (net (code "28") (name "Net-(AMT103_11-PadB)") (class "Default")
      (node (ref "AMT103_11") (pin "B") (pinfunction "B_B") (pintype "bidirectional"))
      (node (ref "SLAVE_MICRO_21") (pin "PD6") (pinfunction "PD6_PD6") (pintype "bidirectional"))
      (node (ref "SLAVE_MICRO_22") (pin "PD6") (pinfunction "PD6_PD6") (pintype "bidirectional"))
    )
    (net (code "29") (name "Net-(AMT103_12-PadA)") (class "Default")
      (node (ref "AMT103_12") (pin "A") (pinfunction "A_A") (pintype "bidirectional"))
      (node (ref "SLAVE_MICRO_23") (pin "PD7") (pinfunction "PD7_PD7") (pintype "bidirectional"))
      (node (ref "SLAVE_MICRO_24") (pin "PD7") (pinfunction "PD7_PD7") (pintype "bidirectional"))
    )
    (net (code "30") (name "Net-(AMT103_12-PadB)") (class "Default")
      (node (ref "AMT103_12") (pin "B") (pinfunction "B_B") (pintype "bidirectional"))
      (node (ref "SLAVE_MICRO_23") (pin "PD6") (pinfunction "PD6_PD6") (pintype "bidirectional"))
      (node (ref "SLAVE_MICRO_24") (pin "PD6") (pinfunction "PD6_PD6") (pintype "bidirectional"))
    )
    (net (code "31") (name "Net-(MASTER_MICRO-PadA)") (class "Default")
      (node (ref "MASTER_MICRO") (pin "A") (pinfunction "A_A") (pintype "bidirectional"))
      (node (ref "MUX_CH64_IC") (pin "A") (pinfunction "A_A") (pintype "bidirectional"))
    )
    (net (code "32") (name "Net-(MASTER_MICRO-PadB)") (class "Default")
      (node (ref "MASTER_MICRO") (pin "B") (pinfunction "B_B") (pintype "bidirectional"))
      (node (ref "MUX_CH64_IC") (pin "B") (pinfunction "B_B") (pintype "bidirectional"))
    )
    (net (code "33") (name "Net-(MASTER_MICRO-PadC)") (class "Default")
      (node (ref "MASTER_MICRO") (pin "C") (pinfunction "C_C") (pintype "bidirectional"))
      (node (ref "MUX_CH64_IC") (pin "C") (pinfunction "C_C") (pintype "bidirectional"))
    )
    (net (code "34") (name "Net-(MASTER_MICRO-PadD)") (class "Default")
      (node (ref "MASTER_MICRO") (pin "D") (pinfunction "D_D") (pintype "bidirectional"))
      (node (ref "MUX_CH64_IC") (pin "D") (pinfunction "D_D") (pintype "bidirectional"))
    )
    (net (code "35") (name "Net-(MASTER_MICRO-PadE)") (class "Default")
      (node (ref "MASTER_MICRO") (pin "E") (pinfunction "E_E") (pintype "bidirectional"))
      (node (ref "MUX_CH64_IC") (pin "E") (pinfunction "E_E") (pintype "bidirectional"))
    )
    (net (code "36") (name "Net-(MASTER_MICRO-PadF)") (class "Default")
      (node (ref "MASTER_MICRO") (pin "F") (pinfunction "F_F") (pintype "bidirectional"))
      (node (ref "MUX_CH64_IC") (pin "F") (pinfunction "F_F") (pintype "bidirectional"))
    )
    (net (code "37") (name "Net-(MUX_CH64_IC-PadO38)") (class "Default")
      (node (ref "MUX_CH64_IC") (pin "O38") (pinfunction "O38_O38") (pintype "bidirectional"))
      (node (ref "SLAVE_MICRO_1") (pin "SS") (pinfunction "SS_SS") (pintype "bidirectional"))
    )
    (net (code "38") (name "Net-(MUX_CH64_IC-PadO39)") (class "Default")
      (node (ref "MUX_CH64_IC") (pin "O39") (pinfunction "O39_O39") (pintype "bidirectional"))
      (node (ref "SLAVE_MICRO_2") (pin "SS") (pinfunction "SS_SS") (pintype "bidirectional"))
    )
    (net (code "39") (name "Net-(MUX_CH64_IC-PadO40)") (class "Default")
      (node (ref "MUX_CH64_IC") (pin "O40") (pinfunction "O40_O40") (pintype "bidirectional"))
      (node (ref "SLAVE_MICRO_3") (pin "SS") (pinfunction "SS_SS") (pintype "bidirectional"))
    )
    (net (code "40") (name "Net-(MUX_CH64_IC-PadO41)") (class "Default")
      (node (ref "MUX_CH64_IC") (pin "O41") (pinfunction "O41_O41") (pintype "bidirectional"))
      (node (ref "SLAVE_MICRO_4") (pin "SS") (pinfunction "SS_SS") (pintype "bidirectional"))
    )
    (net (code "41") (name "Net-(MUX_CH64_IC-PadO42)") (class "Default")
      (node (ref "MUX_CH64_IC") (pin "O42") (pinfunction "O42_O42") (pintype "bidirectional"))
      (node (ref "SLAVE_MICRO_5") (pin "SS") (pinfunction "SS_SS") (pintype "bidirectional"))
    )
    (net (code "42") (name "Net-(MUX_CH64_IC-PadO43)") (class "Default")
      (node (ref "MUX_CH64_IC") (pin "O43") (pinfunction "O43_O43") (pintype "bidirectional"))
      (node (ref "SLAVE_MICRO_6") (pin "SS") (pinfunction "SS_SS") (pintype "bidirectional"))
    )
    (net (code "43") (name "Net-(MUX_CH64_IC-PadO44)") (class "Default")
      (node (ref "MUX_CH64_IC") (pin "O44") (pinfunction "O44_O44") (pintype "bidirectional"))
      (node (ref "SLAVE_MICRO_7") (pin "SS") (pinfunction "SS_SS") (pintype "bidirectional"))
    )
    (net (code "44") (name "Net-(MUX_CH64_IC-PadO45)") (class "Default")
      (node (ref "MUX_CH64_IC") (pin "O45") (pinfunction "O45_O45") (pintype "bidirectional"))
      (node (ref "SLAVE_MICRO_8") (pin "SS") (pinfunction "SS_SS") (pintype "bidirectional"))
    )
    (net (code "45") (name "Net-(MUX_CH64_IC-PadO46)") (class "Default")
      (node (ref "MUX_CH64_IC") (pin "O46") (pinfunction "O46_O46") (pintype "bidirectional"))
      (node (ref "SLAVE_MICRO_9") (pin "SS") (pinfunction "SS_SS") (pintype "bidirectional"))
    )
    (net (code "46") (name "Net-(MUX_CH64_IC-PadO47)") (class "Default")
      (node (ref "MUX_CH64_IC") (pin "O47") (pinfunction "O47_O47") (pintype "bidirectional"))
      (node (ref "SLAVE_MICRO_10") (pin "SS") (pinfunction "SS_SS") (pintype "bidirectional"))
    )
    (net (code "47") (name "Net-(MUX_CH64_IC-PadO48)") (class "Default")
      (node (ref "MUX_CH64_IC") (pin "O48") (pinfunction "O48_O48") (pintype "bidirectional"))
      (node (ref "SLAVE_MICRO_11") (pin "SS") (pinfunction "SS_SS") (pintype "bidirectional"))
    )
    (net (code "48") (name "Net-(MUX_CH64_IC-PadO49)") (class "Default")
      (node (ref "MUX_CH64_IC") (pin "O49") (pinfunction "O49_O49") (pintype "bidirectional"))
      (node (ref "SLAVE_MICRO_12") (pin "SS") (pinfunction "SS_SS") (pintype "bidirectional"))
    )
    (net (code "49") (name "Net-(MUX_CH64_IC-PadO50)") (class "Default")
      (node (ref "MUX_CH64_IC") (pin "O50") (pinfunction "O50_O50") (pintype "bidirectional"))
      (node (ref "SLAVE_MICRO_13") (pin "SS") (pinfunction "SS_SS") (pintype "bidirectional"))
    )
    (net (code "50") (name "Net-(MUX_CH64_IC-PadO51)") (class "Default")
      (node (ref "MUX_CH64_IC") (pin "O51") (pinfunction "O51_O51") (pintype "bidirectional"))
      (node (ref "SLAVE_MICRO_14") (pin "SS") (pinfunction "SS_SS") (pintype "bidirectional"))
    )
    (net (code "51") (name "Net-(MUX_CH64_IC-PadO52)") (class "Default")
      (node (ref "MUX_CH64_IC") (pin "O52") (pinfunction "O52_O52") (pintype "bidirectional"))
      (node (ref "SLAVE_MICRO_15") (pin "SS") (pinfunction "SS_SS") (pintype "bidirectional"))
    )
    (net (code "52") (name "Net-(MUX_CH64_IC-PadO53)") (class "Default")
      (node (ref "MUX_CH64_IC") (pin "O53") (pinfunction "O53_O53") (pintype "bidirectional"))
      (node (ref "SLAVE_MICRO_16") (pin "SS") (pinfunction "SS_SS") (pintype "bidirectional"))
    )
    (net (code "53") (name "Net-(MUX_CH64_IC-PadO54)") (class "Default")
      (node (ref "MUX_CH64_IC") (pin "O54") (pinfunction "O54_O54") (pintype "bidirectional"))
      (node (ref "SLAVE_MICRO_17") (pin "SS") (pinfunction "SS_SS") (pintype "bidirectional"))
    )
    (net (code "54") (name "Net-(MUX_CH64_IC-PadO55)") (class "Default")
      (node (ref "MUX_CH64_IC") (pin "O55") (pinfunction "O55_O55") (pintype "bidirectional"))
      (node (ref "SLAVE_MICRO_18") (pin "SS") (pinfunction "SS_SS") (pintype "bidirectional"))
    )
    (net (code "55") (name "Net-(MUX_CH64_IC-PadO56)") (class "Default")
      (node (ref "MUX_CH64_IC") (pin "O56") (pinfunction "O56_O56") (pintype "bidirectional"))
      (node (ref "SLAVE_MICRO_19") (pin "SS") (pinfunction "SS_SS") (pintype "bidirectional"))
    )
    (net (code "56") (name "Net-(MUX_CH64_IC-PadO57)") (class "Default")
      (node (ref "MUX_CH64_IC") (pin "O57") (pinfunction "O57_O57") (pintype "bidirectional"))
      (node (ref "SLAVE_MICRO_20") (pin "SS") (pinfunction "SS_SS") (pintype "bidirectional"))
    )
    (net (code "57") (name "Net-(MUX_CH64_IC-PadO58)") (class "Default")
      (node (ref "MUX_CH64_IC") (pin "O58") (pinfunction "O58_O58") (pintype "bidirectional"))
      (node (ref "SLAVE_MICRO_21") (pin "SS") (pinfunction "SS_SS") (pintype "bidirectional"))
    )
    (net (code "58") (name "Net-(MUX_CH64_IC-PadO59)") (class "Default")
      (node (ref "MUX_CH64_IC") (pin "O59") (pinfunction "O59_O59") (pintype "bidirectional"))
      (node (ref "SLAVE_MICRO_22") (pin "SS") (pinfunction "SS_SS") (pintype "bidirectional"))
    )
    (net (code "59") (name "Net-(MUX_CH64_IC-PadO60)") (class "Default")
      (node (ref "MUX_CH64_IC") (pin "O60") (pinfunction "O60_O60") (pintype "bidirectional"))
      (node (ref "SLAVE_MICRO_23") (pin "SS") (pinfunction "SS_SS") (pintype "bidirectional"))
    )
    (net (code "60") (name "Net-(MUX_CH64_IC-PadO61)") (class "Default")
      (node (ref "MUX_CH64_IC") (pin "O61") (pinfunction "O61_O61") (pintype "bidirectional"))
      (node (ref "SLAVE_MICRO_24") (pin "SS") (pinfunction "SS_SS") (pintype "bidirectional"))
    )
    (net (code "61") (name "Net-(PRESSURE_SENSOR_1-V_OUT)") (class "Default")
      (node (ref "PRESSURE_SENSOR_1") (pin "1") (pinfunction "V_OUT_1") (pintype "bidirectional"))
      (node (ref "SLAVE_MICRO_1") (pin "PR1") (pinfunction "PR1_PR1") (pintype "bidirectional"))
      (node (ref "SLAVE_MICRO_2") (pin "PR2") (pinfunction "PR2_PR2") (pintype "bidirectional"))
    )
    (net (code "62") (name "Net-(PRESSURE_SENSOR_2-V_OUT)") (class "Default")
      (node (ref "PRESSURE_SENSOR_2") (pin "1") (pinfunction "V_OUT_1") (pintype "bidirectional"))
      (node (ref "SLAVE_MICRO_1") (pin "PR2") (pinfunction "PR2_PR2") (pintype "bidirectional"))
      (node (ref "SLAVE_MICRO_2") (pin "PR1") (pinfunction "PR1_PR1") (pintype "bidirectional"))
    )
    (net (code "63") (name "Net-(PRESSURE_SENSOR_3-V_OUT)") (class "Default")
      (node (ref "PRESSURE_SENSOR_3") (pin "1") (pinfunction "V_OUT_1") (pintype "bidirectional"))
      (node (ref "SLAVE_MICRO_3") (pin "PR1") (pinfunction "PR1_PR1") (pintype "bidirectional"))
      (node (ref "SLAVE_MICRO_4") (pin "PR2") (pinfunction "PR2_PR2") (pintype "bidirectional"))
    )
    (net (code "64") (name "Net-(PRESSURE_SENSOR_4-V_OUT)") (class "Default")
      (node (ref "PRESSURE_SENSOR_4") (pin "1") (pinfunction "V_OUT_1") (pintype "bidirectional"))
      (node (ref "SLAVE_MICRO_3") (pin "PR2") (pinfunction "PR2_PR2") (pintype "bidirectional"))
      (node (ref "SLAVE_MICRO_4") (pin "PR1") (pinfunction "PR1_PR1") (pintype "bidirectional"))
    )
    (net (code "65") (name "Net-(PRESSURE_SENSOR_5-V_OUT)") (class "Default")
      (node (ref "PRESSURE_SENSOR_5") (pin "1") (pinfunction "V_OUT_1") (pintype "bidirectional"))
      (node (ref "SLAVE_MICRO_5") (pin "PR1") (pinfunction "PR1_PR1") (pintype "bidirectional"))
      (node (ref "SLAVE_MICRO_6") (pin "PR2") (pinfunction "PR2_PR2") (pintype "bidirectional"))
    )
    (net (code "66") (name "Net-(PRESSURE_SENSOR_6-V_OUT)") (class "Default")
      (node (ref "PRESSURE_SENSOR_6") (pin "1") (pinfunction "V_OUT_1") (pintype "bidirectional"))
      (node (ref "SLAVE_MICRO_5") (pin "PR2") (pinfunction "PR2_PR2") (pintype "bidirectional"))
      (node (ref "SLAVE_MICRO_6") (pin "PR1") (pinfunction "PR1_PR1") (pintype "bidirectional"))
    )
    (net (code "67") (name "Net-(PRESSURE_SENSOR_7-V_OUT)") (class "Default")
      (node (ref "PRESSURE_SENSOR_7") (pin "1") (pinfunction "V_OUT_1") (pintype "bidirectional"))
      (node (ref "SLAVE_MICRO_7") (pin "PR1") (pinfunction "PR1_PR1") (pintype "bidirectional"))
      (node (ref "SLAVE_MICRO_8") (pin "PR2") (pinfunction "PR2_PR2") (pintype "bidirectional"))
    )
    (net (code "68") (name "Net-(PRESSURE_SENSOR_8-V_OUT)") (class "Default")
      (node (ref "PRESSURE_SENSOR_8") (pin "1") (pinfunction "V_OUT_1") (pintype "bidirectional"))
      (node (ref "SLAVE_MICRO_7") (pin "PR2") (pinfunction "PR2_PR2") (pintype "bidirectional"))
      (node (ref "SLAVE_MICRO_8") (pin "PR1") (pinfunction "PR1_PR1") (pintype "bidirectional"))
    )
    (net (code "69") (name "Net-(PRESSURE_SENSOR_9-V_OUT)") (class "Default")
      (node (ref "PRESSURE_SENSOR_9") (pin "1") (pinfunction "V_OUT_1") (pintype "bidirectional"))
      (node (ref "SLAVE_MICRO_10") (pin "PR2") (pinfunction "PR2_PR2") (pintype "bidirectional"))
      (node (ref "SLAVE_MICRO_9") (pin "PR1") (pinfunction "PR1_PR1") (pintype "bidirectional"))
    )
    (net (code "70") (name "Net-(PRESSURE_SENSOR_10-V_OUT)") (class "Default")
      (node (ref "PRESSURE_SENSOR_10") (pin "1") (pinfunction "V_OUT_1") (pintype "bidirectional"))
      (node (ref "SLAVE_MICRO_10") (pin "PR1") (pinfunction "PR1_PR1") (pintype "bidirectional"))
      (node (ref "SLAVE_MICRO_9") (pin "PR2") (pinfunction "PR2_PR2") (pintype "bidirectional"))
    )
    (net (code "71") (name "Net-(PRESSURE_SENSOR_11-V_OUT)") (class "Default")
      (node (ref "PRESSURE_SENSOR_11") (pin "1") (pinfunction "V_OUT_1") (pintype "bidirectional"))
      (node (ref "SLAVE_MICRO_11") (pin "PR1") (pinfunction "PR1_PR1") (pintype "bidirectional"))
      (node (ref "SLAVE_MICRO_12") (pin "PR2") (pinfunction "PR2_PR2") (pintype "bidirectional"))
    )
    (net (code "72") (name "Net-(PRESSURE_SENSOR_12-V_OUT)") (class "Default")
      (node (ref "PRESSURE_SENSOR_12") (pin "1") (pinfunction "V_OUT_1") (pintype "bidirectional"))
      (node (ref "SLAVE_MICRO_11") (pin "PR2") (pinfunction "PR2_PR2") (pintype "bidirectional"))
      (node (ref "SLAVE_MICRO_12") (pin "PR1") (pinfunction "PR1_PR1") (pintype "bidirectional"))
    )
    (net (code "73") (name "Net-(PRESSURE_SENSOR_13-V_OUT)") (class "Default")
      (node (ref "PRESSURE_SENSOR_13") (pin "1") (pinfunction "V_OUT_1") (pintype "bidirectional"))
      (node (ref "SLAVE_MICRO_13") (pin "PR1") (pinfunction "PR1_PR1") (pintype "bidirectional"))
      (node (ref "SLAVE_MICRO_14") (pin "PR2") (pinfunction "PR2_PR2") (pintype "bidirectional"))
    )
    (net (code "74") (name "Net-(PRESSURE_SENSOR_14-V_OUT)") (class "Default")
      (node (ref "PRESSURE_SENSOR_14") (pin "1") (pinfunction "V_OUT_1") (pintype "bidirectional"))
      (node (ref "SLAVE_MICRO_13") (pin "PR2") (pinfunction "PR2_PR2") (pintype "bidirectional"))
      (node (ref "SLAVE_MICRO_14") (pin "PR1") (pinfunction "PR1_PR1") (pintype "bidirectional"))
    )
    (net (code "75") (name "Net-(PRESSURE_SENSOR_15-V_OUT)") (class "Default")
      (node (ref "PRESSURE_SENSOR_15") (pin "1") (pinfunction "V_OUT_1") (pintype "bidirectional"))
      (node (ref "SLAVE_MICRO_15") (pin "PR1") (pinfunction "PR1_PR1") (pintype "bidirectional"))
      (node (ref "SLAVE_MICRO_16") (pin "PR2") (pinfunction "PR2_PR2") (pintype "bidirectional"))
    )
    (net (code "76") (name "Net-(PRESSURE_SENSOR_16-V_OUT)") (class "Default")
      (node (ref "PRESSURE_SENSOR_16") (pin "1") (pinfunction "V_OUT_1") (pintype "bidirectional"))
      (node (ref "SLAVE_MICRO_15") (pin "PR2") (pinfunction "PR2_PR2") (pintype "bidirectional"))
      (node (ref "SLAVE_MICRO_16") (pin "PR1") (pinfunction "PR1_PR1") (pintype "bidirectional"))
    )
    (net (code "77") (name "Net-(PRESSURE_SENSOR_17-V_OUT)") (class "Default")
      (node (ref "PRESSURE_SENSOR_17") (pin "1") (pinfunction "V_OUT_1") (pintype "bidirectional"))
      (node (ref "SLAVE_MICRO_17") (pin "PR1") (pinfunction "PR1_PR1") (pintype "bidirectional"))
      (node (ref "SLAVE_MICRO_18") (pin "PR2") (pinfunction "PR2_PR2") (pintype "bidirectional"))
    )
    (net (code "78") (name "Net-(PRESSURE_SENSOR_18-V_OUT)") (class "Default")
      (node (ref "PRESSURE_SENSOR_18") (pin "1") (pinfunction "V_OUT_1") (pintype "bidirectional"))
      (node (ref "SLAVE_MICRO_17") (pin "PR2") (pinfunction "PR2_PR2") (pintype "bidirectional"))
      (node (ref "SLAVE_MICRO_18") (pin "PR1") (pinfunction "PR1_PR1") (pintype "bidirectional"))
    )
    (net (code "79") (name "Net-(PRESSURE_SENSOR_19-V_OUT)") (class "Default")
      (node (ref "PRESSURE_SENSOR_19") (pin "1") (pinfunction "V_OUT_1") (pintype "bidirectional"))
      (node (ref "SLAVE_MICRO_19") (pin "PR1") (pinfunction "PR1_PR1") (pintype "bidirectional"))
      (node (ref "SLAVE_MICRO_20") (pin "PR2") (pinfunction "PR2_PR2") (pintype "bidirectional"))
    )
    (net (code "80") (name "Net-(PRESSURE_SENSOR_20-V_OUT)") (class "Default")
      (node (ref "PRESSURE_SENSOR_20") (pin "1") (pinfunction "V_OUT_1") (pintype "bidirectional"))
      (node (ref "SLAVE_MICRO_19") (pin "PR2") (pinfunction "PR2_PR2") (pintype "bidirectional"))
      (node (ref "SLAVE_MICRO_20") (pin "PR1") (pinfunction "PR1_PR1") (pintype "bidirectional"))
    )
    (net (code "81") (name "Net-(PRESSURE_SENSOR_21-V_OUT)") (class "Default")
      (node (ref "PRESSURE_SENSOR_21") (pin "1") (pinfunction "V_OUT_1") (pintype "bidirectional"))
      (node (ref "SLAVE_MICRO_21") (pin "PR1") (pinfunction "PR1_PR1") (pintype "bidirectional"))
      (node (ref "SLAVE_MICRO_22") (pin "PR2") (pinfunction "PR2_PR2") (pintype "bidirectional"))
    )
    (net (code "82") (name "Net-(PRESSURE_SENSOR_22-V_OUT)") (class "Default")
      (node (ref "PRESSURE_SENSOR_22") (pin "1") (pinfunction "V_OUT_1") (pintype "bidirectional"))
      (node (ref "SLAVE_MICRO_21") (pin "PR2") (pinfunction "PR2_PR2") (pintype "bidirectional"))
      (node (ref "SLAVE_MICRO_22") (pin "PR1") (pinfunction "PR1_PR1") (pintype "bidirectional"))
    )
    (net (code "83") (name "Net-(PRESSURE_SENSOR_23-V_OUT)") (class "Default")
      (node (ref "PRESSURE_SENSOR_23") (pin "1") (pinfunction "V_OUT_1") (pintype "bidirectional"))
      (node (ref "SLAVE_MICRO_23") (pin "PR1") (pinfunction "PR1_PR1") (pintype "bidirectional"))
      (node (ref "SLAVE_MICRO_24") (pin "PR2") (pinfunction "PR2_PR2") (pintype "bidirectional"))
    )
    (net (code "84") (name "Net-(PRESSURE_SENSOR_24-V_OUT)") (class "Default")
      (node (ref "PRESSURE_SENSOR_24") (pin "1") (pinfunction "V_OUT_1") (pintype "bidirectional"))
      (node (ref "SLAVE_MICRO_23") (pin "PR2") (pinfunction "PR2_PR2") (pintype "bidirectional"))
      (node (ref "SLAVE_MICRO_24") (pin "PR1") (pinfunction "PR1_PR1") (pintype "bidirectional"))
    )
    (net (code "85") (name "Net-(SLAVE_MICRO_1-PadVALVE)") (class "Default")
      (node (ref "SLAVE_MICRO_1") (pin "VALVE") (pinfunction "VALVE_VALVE") (pintype "bidirectional"))
      (node (ref "U$2") (pin "VALVE_IN1") (pinfunction "VALVE_IN1_VALVE_IN1") (pintype "bidirectional"))
    )
    (net (code "86") (name "Net-(SLAVE_MICRO_2-PadVALVE)") (class "Default")
      (node (ref "SLAVE_MICRO_2") (pin "VALVE") (pinfunction "VALVE_VALVE") (pintype "bidirectional"))
      (node (ref "U$2") (pin "VALVE_IN2") (pinfunction "VALVE_IN2_VALVE_IN2") (pintype "bidirectional"))
    )
    (net (code "87") (name "Net-(SLAVE_MICRO_3-PadVALVE)") (class "Default")
      (node (ref "SLAVE_MICRO_3") (pin "VALVE") (pinfunction "VALVE_VALVE") (pintype "bidirectional"))
      (node (ref "U$2") (pin "VALVE_IN3") (pinfunction "VALVE_IN3_VALVE_IN3") (pintype "bidirectional"))
    )
    (net (code "88") (name "Net-(SLAVE_MICRO_4-PadVALVE)") (class "Default")
      (node (ref "SLAVE_MICRO_4") (pin "VALVE") (pinfunction "VALVE_VALVE") (pintype "bidirectional"))
      (node (ref "U$2") (pin "VALVE_IN4") (pinfunction "VALVE_IN4_VALVE_IN4") (pintype "bidirectional"))
    )
    (net (code "89") (name "Net-(SLAVE_MICRO_5-PadVALVE)") (class "Default")
      (node (ref "SLAVE_MICRO_5") (pin "VALVE") (pinfunction "VALVE_VALVE") (pintype "bidirectional"))
      (node (ref "U$2") (pin "VALVE_IN5") (pinfunction "VALVE_IN5_VALVE_IN5") (pintype "bidirectional"))
    )
    (net (code "90") (name "Net-(SLAVE_MICRO_6-PadVALVE)") (class "Default")
      (node (ref "SLAVE_MICRO_6") (pin "VALVE") (pinfunction "VALVE_VALVE") (pintype "bidirectional"))
      (node (ref "U$2") (pin "VALVE_IN6") (pinfunction "VALVE_IN6_VALVE_IN6") (pintype "bidirectional"))
    )
    (net (code "91") (name "Net-(SLAVE_MICRO_7-PadVALVE)") (class "Default")
      (node (ref "SLAVE_MICRO_7") (pin "VALVE") (pinfunction "VALVE_VALVE") (pintype "bidirectional"))
      (node (ref "U$2") (pin "VALVE_IN7") (pinfunction "VALVE_IN7_VALVE_IN7") (pintype "bidirectional"))
    )
    (net (code "92") (name "Net-(SLAVE_MICRO_8-PadVALVE)") (class "Default")
      (node (ref "SLAVE_MICRO_8") (pin "VALVE") (pinfunction "VALVE_VALVE") (pintype "bidirectional"))
      (node (ref "U$2") (pin "VALVE_IN8") (pinfunction "VALVE_IN8_VALVE_IN8") (pintype "bidirectional"))
    )
    (net (code "93") (name "Net-(SLAVE_MICRO_9-PadVALVE)") (class "Default")
      (node (ref "SLAVE_MICRO_9") (pin "VALVE") (pinfunction "VALVE_VALVE") (pintype "bidirectional"))
      (node (ref "U$2") (pin "VALVE_IN9") (pinfunction "VALVE_IN9_VALVE_IN9") (pintype "bidirectional"))
    )
    (net (code "94") (name "Net-(SLAVE_MICRO_10-PadVALVE)") (class "Default")
      (node (ref "SLAVE_MICRO_10") (pin "VALVE") (pinfunction "VALVE_VALVE") (pintype "bidirectional"))
      (node (ref "U$2") (pin "VALVE_IN10") (pinfunction "VALVE_IN10_VALVE_IN10") (pintype "bidirectional"))
    )
    (net (code "95") (name "Net-(SLAVE_MICRO_11-PadVALVE)") (class "Default")
      (node (ref "SLAVE_MICRO_11") (pin "VALVE") (pinfunction "VALVE_VALVE") (pintype "bidirectional"))
      (node (ref "U$2") (pin "VALVE_IN11") (pinfunction "VALVE_IN11_VALVE_IN11") (pintype "bidirectional"))
    )
    (net (code "96") (name "Net-(SLAVE_MICRO_12-PadVALVE)") (class "Default")
      (node (ref "SLAVE_MICRO_12") (pin "VALVE") (pinfunction "VALVE_VALVE") (pintype "bidirectional"))
      (node (ref "U$2") (pin "VALVE_IN12") (pinfunction "VALVE_IN12_VALVE_IN12") (pintype "bidirectional"))
    )
    (net (code "97") (name "Net-(SLAVE_MICRO_13-PadVALVE)") (class "Default")
      (node (ref "SLAVE_MICRO_13") (pin "VALVE") (pinfunction "VALVE_VALVE") (pintype "bidirectional"))
      (node (ref "U$2") (pin "VALVE_IN13") (pinfunction "VALVE_IN13_VALVE_IN13") (pintype "bidirectional"))
    )
    (net (code "98") (name "Net-(SLAVE_MICRO_14-PadVALVE)") (class "Default")
      (node (ref "SLAVE_MICRO_14") (pin "VALVE") (pinfunction "VALVE_VALVE") (pintype "bidirectional"))
      (node (ref "U$2") (pin "VALVE_IN14") (pinfunction "VALVE_IN14_VALVE_IN14") (pintype "bidirectional"))
    )
    (net (code "99") (name "Net-(SLAVE_MICRO_15-PadVALVE)") (class "Default")
      (node (ref "SLAVE_MICRO_15") (pin "VALVE") (pinfunction "VALVE_VALVE") (pintype "bidirectional"))
      (node (ref "U$2") (pin "VALVE_IN15") (pinfunction "VALVE_IN15_VALVE_IN15") (pintype "bidirectional"))
    )
    (net (code "100") (name "Net-(SLAVE_MICRO_16-PadVALVE)") (class "Default")
      (node (ref "SLAVE_MICRO_16") (pin "VALVE") (pinfunction "VALVE_VALVE") (pintype "bidirectional"))
      (node (ref "U$2") (pin "VALVE_IN16") (pinfunction "VALVE_IN16_VALVE_IN16") (pintype "bidirectional"))
    )
    (net (code "101") (name "Net-(SLAVE_MICRO_17-PadVALVE)") (class "Default")
      (node (ref "SLAVE_MICRO_17") (pin "VALVE") (pinfunction "VALVE_VALVE") (pintype "bidirectional"))
      (node (ref "U$2") (pin "VALVE_IN17") (pinfunction "VALVE_IN17_VALVE_IN17") (pintype "bidirectional"))
    )
    (net (code "102") (name "Net-(SLAVE_MICRO_18-PadVALVE)") (class "Default")
      (node (ref "SLAVE_MICRO_18") (pin "VALVE") (pinfunction "VALVE_VALVE") (pintype "bidirectional"))
      (node (ref "U$2") (pin "VALVE_IN18") (pinfunction "VALVE_IN18_VALVE_IN18") (pintype "bidirectional"))
    )
    (net (code "103") (name "Net-(SLAVE_MICRO_19-PadVALVE)") (class "Default")
      (node (ref "SLAVE_MICRO_19") (pin "VALVE") (pinfunction "VALVE_VALVE") (pintype "bidirectional"))
      (node (ref "U$2") (pin "VALVE_IN19") (pinfunction "VALVE_IN19_VALVE_IN19") (pintype "bidirectional"))
    )
    (net (code "104") (name "Net-(SLAVE_MICRO_20-PadVALVE)") (class "Default")
      (node (ref "SLAVE_MICRO_20") (pin "VALVE") (pinfunction "VALVE_VALVE") (pintype "bidirectional"))
      (node (ref "U$2") (pin "VALVE_IN20") (pinfunction "VALVE_IN20_VALVE_IN20") (pintype "bidirectional"))
    )
    (net (code "105") (name "Net-(SLAVE_MICRO_21-PadVALVE)") (class "Default")
      (node (ref "SLAVE_MICRO_21") (pin "VALVE") (pinfunction "VALVE_VALVE") (pintype "bidirectional"))
      (node (ref "U$2") (pin "VALVE_IN21") (pinfunction "VALVE_IN21_VALVE_IN21") (pintype "bidirectional"))
    )
    (net (code "106") (name "Net-(SLAVE_MICRO_22-PadVALVE)") (class "Default")
      (node (ref "SLAVE_MICRO_22") (pin "VALVE") (pinfunction "VALVE_VALVE") (pintype "bidirectional"))
      (node (ref "U$2") (pin "VALVE_IN22") (pinfunction "VALVE_IN22_VALVE_IN22") (pintype "bidirectional"))
    )
    (net (code "107") (name "Net-(SLAVE_MICRO_23-PadVALVE)") (class "Default")
      (node (ref "SLAVE_MICRO_23") (pin "VALVE") (pinfunction "VALVE_VALVE") (pintype "bidirectional"))
      (node (ref "U$2") (pin "VALVE_IN23") (pinfunction "VALVE_IN23_VALVE_IN23") (pintype "bidirectional"))
    )
    (net (code "108") (name "Net-(SLAVE_MICRO_24-PadVALVE)") (class "Default")
      (node (ref "SLAVE_MICRO_24") (pin "VALVE") (pinfunction "VALVE_VALVE") (pintype "bidirectional"))
      (node (ref "U$2") (pin "VALVE_IN24") (pinfunction "VALVE_IN24_VALVE_IN24") (pintype "bidirectional"))
    )
    (net (code "109") (name "SCK") (class "Default")
      (node (ref "MASTER_MICRO") (pin "SCK") (pinfunction "SCK_SCK") (pintype "bidirectional"))
      (node (ref "SLAVE_MICRO_1") (pin "SCK") (pinfunction "SCK_SCK") (pintype "bidirectional"))
      (node (ref "SLAVE_MICRO_10") (pin "SCK") (pinfunction "SCK_SCK") (pintype "bidirectional"))
      (node (ref "SLAVE_MICRO_11") (pin "SCK") (pinfunction "SCK_SCK") (pintype "bidirectional"))
      (node (ref "SLAVE_MICRO_12") (pin "SCK") (pinfunction "SCK_SCK") (pintype "bidirectional"))
      (node (ref "SLAVE_MICRO_13") (pin "SCK") (pinfunction "SCK_SCK") (pintype "bidirectional"))
      (node (ref "SLAVE_MICRO_14") (pin "SCK") (pinfunction "SCK_SCK") (pintype "bidirectional"))
      (node (ref "SLAVE_MICRO_15") (pin "SCK") (pinfunction "SCK_SCK") (pintype "bidirectional"))
      (node (ref "SLAVE_MICRO_16") (pin "SCK") (pinfunction "SCK_SCK") (pintype "bidirectional"))
      (node (ref "SLAVE_MICRO_17") (pin "SCK") (pinfunction "SCK_SCK") (pintype "bidirectional"))
      (node (ref "SLAVE_MICRO_18") (pin "SCK") (pinfunction "SCK_SCK") (pintype "bidirectional"))
      (node (ref "SLAVE_MICRO_19") (pin "SCK") (pinfunction "SCK_SCK") (pintype "bidirectional"))
      (node (ref "SLAVE_MICRO_2") (pin "SCK") (pinfunction "SCK_SCK") (pintype "bidirectional"))
      (node (ref "SLAVE_MICRO_20") (pin "SCK") (pinfunction "SCK_SCK") (pintype "bidirectional"))
      (node (ref "SLAVE_MICRO_21") (pin "SCK") (pinfunction "SCK_SCK") (pintype "bidirectional"))
      (node (ref "SLAVE_MICRO_22") (pin "SCK") (pinfunction "SCK_SCK") (pintype "bidirectional"))
      (node (ref "SLAVE_MICRO_23") (pin "SCK") (pinfunction "SCK_SCK") (pintype "bidirectional"))
      (node (ref "SLAVE_MICRO_24") (pin "SCK") (pinfunction "SCK_SCK") (pintype "bidirectional"))
      (node (ref "SLAVE_MICRO_3") (pin "SCK") (pinfunction "SCK_SCK") (pintype "bidirectional"))
      (node (ref "SLAVE_MICRO_4") (pin "SCK") (pinfunction "SCK_SCK") (pintype "bidirectional"))
      (node (ref "SLAVE_MICRO_5") (pin "SCK") (pinfunction "SCK_SCK") (pintype "bidirectional"))
      (node (ref "SLAVE_MICRO_6") (pin "SCK") (pinfunction "SCK_SCK") (pintype "bidirectional"))
      (node (ref "SLAVE_MICRO_7") (pin "SCK") (pinfunction "SCK_SCK") (pintype "bidirectional"))
      (node (ref "SLAVE_MICRO_8") (pin "SCK") (pinfunction "SCK_SCK") (pintype "bidirectional"))
      (node (ref "SLAVE_MICRO_9") (pin "SCK") (pinfunction "SCK_SCK") (pintype "bidirectional"))
    )
    (net (code "110") (name "unconnected-(AMT103_1-PadX)") (class "Default")
      (node (ref "AMT103_1") (pin "X") (pinfunction "X_X") (pintype "bidirectional"))
    )
    (net (code "111") (name "unconnected-(AMT103_2-PadX)") (class "Default")
      (node (ref "AMT103_2") (pin "X") (pinfunction "X_X") (pintype "bidirectional"))
    )
    (net (code "112") (name "unconnected-(AMT103_3-PadX)") (class "Default")
      (node (ref "AMT103_3") (pin "X") (pinfunction "X_X") (pintype "bidirectional"))
    )
    (net (code "113") (name "unconnected-(AMT103_4-PadX)") (class "Default")
      (node (ref "AMT103_4") (pin "X") (pinfunction "X_X") (pintype "bidirectional"))
    )
    (net (code "114") (name "unconnected-(AMT103_5-PadX)") (class "Default")
      (node (ref "AMT103_5") (pin "X") (pinfunction "X_X") (pintype "bidirectional"))
    )
    (net (code "115") (name "unconnected-(AMT103_6-PadX)") (class "Default")
      (node (ref "AMT103_6") (pin "X") (pinfunction "X_X") (pintype "bidirectional"))
    )
    (net (code "116") (name "unconnected-(AMT103_7-PadX)") (class "Default")
      (node (ref "AMT103_7") (pin "X") (pinfunction "X_X") (pintype "bidirectional"))
    )
    (net (code "117") (name "unconnected-(AMT103_8-PadX)") (class "Default")
      (node (ref "AMT103_8") (pin "X") (pinfunction "X_X") (pintype "bidirectional"))
    )
    (net (code "118") (name "unconnected-(AMT103_9-PadX)") (class "Default")
      (node (ref "AMT103_9") (pin "X") (pinfunction "X_X") (pintype "bidirectional"))
    )
    (net (code "119") (name "unconnected-(AMT103_10-PadX)") (class "Default")
      (node (ref "AMT103_10") (pin "X") (pinfunction "X_X") (pintype "bidirectional"))
    )
    (net (code "120") (name "unconnected-(AMT103_11-PadX)") (class "Default")
      (node (ref "AMT103_11") (pin "X") (pinfunction "X_X") (pintype "bidirectional"))
    )
    (net (code "121") (name "unconnected-(AMT103_12-PadX)") (class "Default")
      (node (ref "AMT103_12") (pin "X") (pinfunction "X_X") (pintype "bidirectional"))
    )
    (net (code "122") (name "unconnected-(MASTER_MICRO-Pad-24V)") (class "Default")
      (node (ref "MASTER_MICRO") (pin "-24V") (pinfunction "-24V_-24V") (pintype "bidirectional"))
    )
    (net (code "123") (name "unconnected-(MASTER_MICRO-PadADC1)") (class "Default")
      (node (ref "MASTER_MICRO") (pin "ADC1") (pinfunction "ADC1_ADC1") (pintype "bidirectional"))
    )
    (net (code "124") (name "unconnected-(MASTER_MICRO-PadADC2)") (class "Default")
      (node (ref "MASTER_MICRO") (pin "ADC2") (pinfunction "ADC2_ADC2") (pintype "bidirectional"))
    )
    (net (code "125") (name "unconnected-(MASTER_MICRO-PadADC3)") (class "Default")
      (node (ref "MASTER_MICRO") (pin "ADC3") (pinfunction "ADC3_ADC3") (pintype "bidirectional"))
    )
    (net (code "126") (name "unconnected-(MASTER_MICRO-PadADC4)") (class "Default")
      (node (ref "MASTER_MICRO") (pin "ADC4") (pinfunction "ADC4_ADC4") (pintype "bidirectional"))
    )
    (net (code "127") (name "unconnected-(MASTER_MICRO-PadADC5)") (class "Default")
      (node (ref "MASTER_MICRO") (pin "ADC5") (pinfunction "ADC5_ADC5") (pintype "bidirectional"))
    )
    (net (code "128") (name "unconnected-(MASTER_MICRO-PadDAC)") (class "Default")
      (node (ref "MASTER_MICRO") (pin "DAC") (pinfunction "DAC_DAC") (pintype "bidirectional"))
    )
    (net (code "129") (name "unconnected-(MUX_CH64_IC-PadNC)") (class "Default")
      (node (ref "MUX_CH64_IC") (pin "NC") (pinfunction "NC_NC") (pintype "no_connect"))
    )
    (net (code "130") (name "unconnected-(MUX_CH64_IC-PadO0)") (class "Default")
      (node (ref "MUX_CH64_IC") (pin "O0") (pinfunction "O0_O0") (pintype "bidirectional"))
    )
    (net (code "131") (name "unconnected-(MUX_CH64_IC-PadO1)") (class "Default")
      (node (ref "MUX_CH64_IC") (pin "O1") (pinfunction "O1_O1") (pintype "bidirectional"))
    )
    (net (code "132") (name "unconnected-(MUX_CH64_IC-PadO2)") (class "Default")
      (node (ref "MUX_CH64_IC") (pin "O2") (pinfunction "O2_O2") (pintype "bidirectional"))
    )
    (net (code "133") (name "unconnected-(MUX_CH64_IC-PadO3)") (class "Default")
      (node (ref "MUX_CH64_IC") (pin "O3") (pinfunction "O3_O3") (pintype "bidirectional"))
    )
    (net (code "134") (name "unconnected-(MUX_CH64_IC-PadO4)") (class "Default")
      (node (ref "MUX_CH64_IC") (pin "O4") (pinfunction "O4_O4") (pintype "bidirectional"))
    )
    (net (code "135") (name "unconnected-(MUX_CH64_IC-PadO5)") (class "Default")
      (node (ref "MUX_CH64_IC") (pin "O5") (pinfunction "O5_O5") (pintype "bidirectional"))
    )
    (net (code "136") (name "unconnected-(MUX_CH64_IC-PadO6)") (class "Default")
      (node (ref "MUX_CH64_IC") (pin "O6") (pinfunction "O6_O6") (pintype "bidirectional"))
    )
    (net (code "137") (name "unconnected-(MUX_CH64_IC-PadO7)") (class "Default")
      (node (ref "MUX_CH64_IC") (pin "O7") (pinfunction "O7_O7") (pintype "bidirectional"))
    )
    (net (code "138") (name "unconnected-(MUX_CH64_IC-PadO8)") (class "Default")
      (node (ref "MUX_CH64_IC") (pin "O8") (pinfunction "O8_O8") (pintype "bidirectional"))
    )
    (net (code "139") (name "unconnected-(MUX_CH64_IC-PadO9)") (class "Default")
      (node (ref "MUX_CH64_IC") (pin "O9") (pinfunction "O9_O9") (pintype "bidirectional"))
    )
    (net (code "140") (name "unconnected-(MUX_CH64_IC-PadO10)") (class "Default")
      (node (ref "MUX_CH64_IC") (pin "O10") (pinfunction "O10_O10") (pintype "bidirectional"))
    )
    (net (code "141") (name "unconnected-(MUX_CH64_IC-PadO11)") (class "Default")
      (node (ref "MUX_CH64_IC") (pin "O11") (pinfunction "O11_O11") (pintype "bidirectional"))
    )
    (net (code "142") (name "unconnected-(MUX_CH64_IC-PadO12)") (class "Default")
      (node (ref "MUX_CH64_IC") (pin "O12") (pinfunction "O12_O12") (pintype "bidirectional"))
    )
    (net (code "143") (name "unconnected-(MUX_CH64_IC-PadO13)") (class "Default")
      (node (ref "MUX_CH64_IC") (pin "O13") (pinfunction "O13_O13") (pintype "bidirectional"))
    )
    (net (code "144") (name "unconnected-(MUX_CH64_IC-PadO14)") (class "Default")
      (node (ref "MUX_CH64_IC") (pin "O14") (pinfunction "O14_O14") (pintype "bidirectional"))
    )
    (net (code "145") (name "unconnected-(MUX_CH64_IC-PadO15)") (class "Default")
      (node (ref "MUX_CH64_IC") (pin "O15") (pinfunction "O15_O15") (pintype "bidirectional"))
    )
    (net (code "146") (name "unconnected-(MUX_CH64_IC-PadO16)") (class "Default")
      (node (ref "MUX_CH64_IC") (pin "O16") (pinfunction "O16_O16") (pintype "bidirectional"))
    )
    (net (code "147") (name "unconnected-(MUX_CH64_IC-PadO17)") (class "Default")
      (node (ref "MUX_CH64_IC") (pin "O17") (pinfunction "O17_O17") (pintype "bidirectional"))
    )
    (net (code "148") (name "unconnected-(MUX_CH64_IC-PadO18)") (class "Default")
      (node (ref "MUX_CH64_IC") (pin "O18") (pinfunction "O18_O18") (pintype "bidirectional"))
    )
    (net (code "149") (name "unconnected-(MUX_CH64_IC-PadO19)") (class "Default")
      (node (ref "MUX_CH64_IC") (pin "O19") (pinfunction "O19_O19") (pintype "bidirectional"))
    )
    (net (code "150") (name "unconnected-(MUX_CH64_IC-PadO20)") (class "Default")
      (node (ref "MUX_CH64_IC") (pin "O20") (pinfunction "O20_O20") (pintype "bidirectional"))
    )
    (net (code "151") (name "unconnected-(MUX_CH64_IC-PadO21)") (class "Default")
      (node (ref "MUX_CH64_IC") (pin "O21") (pinfunction "O21_O21") (pintype "bidirectional"))
    )
    (net (code "152") (name "unconnected-(MUX_CH64_IC-PadO22)") (class "Default")
      (node (ref "MUX_CH64_IC") (pin "O22") (pinfunction "O22_O22") (pintype "bidirectional"))
    )
    (net (code "153") (name "unconnected-(MUX_CH64_IC-PadO23)") (class "Default")
      (node (ref "MUX_CH64_IC") (pin "O23") (pinfunction "O23_O23") (pintype "bidirectional"))
    )
    (net (code "154") (name "unconnected-(MUX_CH64_IC-PadO24)") (class "Default")
      (node (ref "MUX_CH64_IC") (pin "O24") (pinfunction "O24_O24") (pintype "bidirectional"))
    )
    (net (code "155") (name "unconnected-(MUX_CH64_IC-PadO25)") (class "Default")
      (node (ref "MUX_CH64_IC") (pin "O25") (pinfunction "O25_O25") (pintype "bidirectional"))
    )
    (net (code "156") (name "unconnected-(MUX_CH64_IC-PadO26)") (class "Default")
      (node (ref "MUX_CH64_IC") (pin "O26") (pinfunction "O26_O26") (pintype "bidirectional"))
    )
    (net (code "157") (name "unconnected-(MUX_CH64_IC-PadO27)") (class "Default")
      (node (ref "MUX_CH64_IC") (pin "O27") (pinfunction "O27_O27") (pintype "bidirectional"))
    )
    (net (code "158") (name "unconnected-(MUX_CH64_IC-PadO28)") (class "Default")
      (node (ref "MUX_CH64_IC") (pin "O28") (pinfunction "O28_O28") (pintype "bidirectional"))
    )
    (net (code "159") (name "unconnected-(MUX_CH64_IC-PadO29)") (class "Default")
      (node (ref "MUX_CH64_IC") (pin "O29") (pinfunction "O29_O29") (pintype "bidirectional"))
    )
    (net (code "160") (name "unconnected-(MUX_CH64_IC-PadO30)") (class "Default")
      (node (ref "MUX_CH64_IC") (pin "O30") (pinfunction "O30_O30") (pintype "bidirectional"))
    )
    (net (code "161") (name "unconnected-(MUX_CH64_IC-PadO31)") (class "Default")
      (node (ref "MUX_CH64_IC") (pin "O31") (pinfunction "O31_O31") (pintype "bidirectional"))
    )
    (net (code "162") (name "unconnected-(MUX_CH64_IC-PadO32)") (class "Default")
      (node (ref "MUX_CH64_IC") (pin "O32") (pinfunction "O32_O32") (pintype "bidirectional"))
    )
    (net (code "163") (name "unconnected-(MUX_CH64_IC-PadO33)") (class "Default")
      (node (ref "MUX_CH64_IC") (pin "O33") (pinfunction "O33_O33") (pintype "bidirectional"))
    )
    (net (code "164") (name "unconnected-(MUX_CH64_IC-PadO34)") (class "Default")
      (node (ref "MUX_CH64_IC") (pin "O34") (pinfunction "O34_O34") (pintype "bidirectional"))
    )
    (net (code "165") (name "unconnected-(MUX_CH64_IC-PadO35)") (class "Default")
      (node (ref "MUX_CH64_IC") (pin "O35") (pinfunction "O35_O35") (pintype "bidirectional"))
    )
    (net (code "166") (name "unconnected-(MUX_CH64_IC-PadO36)") (class "Default")
      (node (ref "MUX_CH64_IC") (pin "O36") (pinfunction "O36_O36") (pintype "bidirectional"))
    )
    (net (code "167") (name "unconnected-(MUX_CH64_IC-PadO37)") (class "Default")
      (node (ref "MUX_CH64_IC") (pin "O37") (pinfunction "O37_O37") (pintype "bidirectional"))
    )
    (net (code "168") (name "unconnected-(MUX_CH64_IC-PadO62)") (class "Default")
      (node (ref "MUX_CH64_IC") (pin "O62") (pinfunction "O62_O62") (pintype "bidirectional"))
    )
    (net (code "169") (name "unconnected-(MUX_CH64_IC-PadO63)") (class "Default")
      (node (ref "MUX_CH64_IC") (pin "O63") (pinfunction "O63_O63") (pintype "bidirectional"))
    )
    (net (code "170") (name "unconnected-(PRESSURE_SENSOR_1-V1-Pad4)") (class "Default")
      (node (ref "PRESSURE_SENSOR_1") (pin "4") (pinfunction "V1_4") (pintype "bidirectional"))
    )
    (net (code "171") (name "unconnected-(PRESSURE_SENSOR_1-V2-Pad5)") (class "Default")
      (node (ref "PRESSURE_SENSOR_1") (pin "5") (pinfunction "V2_5") (pintype "bidirectional"))
    )
    (net (code "172") (name "unconnected-(PRESSURE_SENSOR_1-V_EX-Pad6)") (class "Default")
      (node (ref "PRESSURE_SENSOR_1") (pin "6") (pinfunction "V_EX_6") (pintype "bidirectional"))
    )
    (net (code "173") (name "unconnected-(PRESSURE_SENSOR_2-V1-Pad4)") (class "Default")
      (node (ref "PRESSURE_SENSOR_2") (pin "4") (pinfunction "V1_4") (pintype "bidirectional"))
    )
    (net (code "174") (name "unconnected-(PRESSURE_SENSOR_2-V2-Pad5)") (class "Default")
      (node (ref "PRESSURE_SENSOR_2") (pin "5") (pinfunction "V2_5") (pintype "bidirectional"))
    )
    (net (code "175") (name "unconnected-(PRESSURE_SENSOR_2-V_EX-Pad6)") (class "Default")
      (node (ref "PRESSURE_SENSOR_2") (pin "6") (pinfunction "V_EX_6") (pintype "bidirectional"))
    )
    (net (code "176") (name "unconnected-(PRESSURE_SENSOR_3-V1-Pad4)") (class "Default")
      (node (ref "PRESSURE_SENSOR_3") (pin "4") (pinfunction "V1_4") (pintype "bidirectional"))
    )
    (net (code "177") (name "unconnected-(PRESSURE_SENSOR_3-V2-Pad5)") (class "Default")
      (node (ref "PRESSURE_SENSOR_3") (pin "5") (pinfunction "V2_5") (pintype "bidirectional"))
    )
    (net (code "178") (name "unconnected-(PRESSURE_SENSOR_3-V_EX-Pad6)") (class "Default")
      (node (ref "PRESSURE_SENSOR_3") (pin "6") (pinfunction "V_EX_6") (pintype "bidirectional"))
    )
    (net (code "179") (name "unconnected-(PRESSURE_SENSOR_4-V1-Pad4)") (class "Default")
      (node (ref "PRESSURE_SENSOR_4") (pin "4") (pinfunction "V1_4") (pintype "bidirectional"))
    )
    (net (code "180") (name "unconnected-(PRESSURE_SENSOR_4-V2-Pad5)") (class "Default")
      (node (ref "PRESSURE_SENSOR_4") (pin "5") (pinfunction "V2_5") (pintype "bidirectional"))
    )
    (net (code "181") (name "unconnected-(PRESSURE_SENSOR_4-V_EX-Pad6)") (class "Default")
      (node (ref "PRESSURE_SENSOR_4") (pin "6") (pinfunction "V_EX_6") (pintype "bidirectional"))
    )
    (net (code "182") (name "unconnected-(PRESSURE_SENSOR_5-V1-Pad4)") (class "Default")
      (node (ref "PRESSURE_SENSOR_5") (pin "4") (pinfunction "V1_4") (pintype "bidirectional"))
    )
    (net (code "183") (name "unconnected-(PRESSURE_SENSOR_5-V2-Pad5)") (class "Default")
      (node (ref "PRESSURE_SENSOR_5") (pin "5") (pinfunction "V2_5") (pintype "bidirectional"))
    )
    (net (code "184") (name "unconnected-(PRESSURE_SENSOR_5-V_EX-Pad6)") (class "Default")
      (node (ref "PRESSURE_SENSOR_5") (pin "6") (pinfunction "V_EX_6") (pintype "bidirectional"))
    )
    (net (code "185") (name "unconnected-(PRESSURE_SENSOR_6-V1-Pad4)") (class "Default")
      (node (ref "PRESSURE_SENSOR_6") (pin "4") (pinfunction "V1_4") (pintype "bidirectional"))
    )
    (net (code "186") (name "unconnected-(PRESSURE_SENSOR_6-V2-Pad5)") (class "Default")
      (node (ref "PRESSURE_SENSOR_6") (pin "5") (pinfunction "V2_5") (pintype "bidirectional"))
    )
    (net (code "187") (name "unconnected-(PRESSURE_SENSOR_6-V_EX-Pad6)") (class "Default")
      (node (ref "PRESSURE_SENSOR_6") (pin "6") (pinfunction "V_EX_6") (pintype "bidirectional"))
    )
    (net (code "188") (name "unconnected-(PRESSURE_SENSOR_7-V1-Pad4)") (class "Default")
      (node (ref "PRESSURE_SENSOR_7") (pin "4") (pinfunction "V1_4") (pintype "bidirectional"))
    )
    (net (code "189") (name "unconnected-(PRESSURE_SENSOR_7-V2-Pad5)") (class "Default")
      (node (ref "PRESSURE_SENSOR_7") (pin "5") (pinfunction "V2_5") (pintype "bidirectional"))
    )
    (net (code "190") (name "unconnected-(PRESSURE_SENSOR_7-V_EX-Pad6)") (class "Default")
      (node (ref "PRESSURE_SENSOR_7") (pin "6") (pinfunction "V_EX_6") (pintype "bidirectional"))
    )
    (net (code "191") (name "unconnected-(PRESSURE_SENSOR_8-V1-Pad4)") (class "Default")
      (node (ref "PRESSURE_SENSOR_8") (pin "4") (pinfunction "V1_4") (pintype "bidirectional"))
    )
    (net (code "192") (name "unconnected-(PRESSURE_SENSOR_8-V2-Pad5)") (class "Default")
      (node (ref "PRESSURE_SENSOR_8") (pin "5") (pinfunction "V2_5") (pintype "bidirectional"))
    )
    (net (code "193") (name "unconnected-(PRESSURE_SENSOR_8-V_EX-Pad6)") (class "Default")
      (node (ref "PRESSURE_SENSOR_8") (pin "6") (pinfunction "V_EX_6") (pintype "bidirectional"))
    )
    (net (code "194") (name "unconnected-(PRESSURE_SENSOR_9-V1-Pad4)") (class "Default")
      (node (ref "PRESSURE_SENSOR_9") (pin "4") (pinfunction "V1_4") (pintype "bidirectional"))
    )
    (net (code "195") (name "unconnected-(PRESSURE_SENSOR_9-V2-Pad5)") (class "Default")
      (node (ref "PRESSURE_SENSOR_9") (pin "5") (pinfunction "V2_5") (pintype "bidirectional"))
    )
    (net (code "196") (name "unconnected-(PRESSURE_SENSOR_9-V_EX-Pad6)") (class "Default")
      (node (ref "PRESSURE_SENSOR_9") (pin "6") (pinfunction "V_EX_6") (pintype "bidirectional"))
    )
    (net (code "197") (name "unconnected-(PRESSURE_SENSOR_10-V1-Pad4)") (class "Default")
      (node (ref "PRESSURE_SENSOR_10") (pin "4") (pinfunction "V1_4") (pintype "bidirectional"))
    )
    (net (code "198") (name "unconnected-(PRESSURE_SENSOR_10-V2-Pad5)") (class "Default")
      (node (ref "PRESSURE_SENSOR_10") (pin "5") (pinfunction "V2_5") (pintype "bidirectional"))
    )
    (net (code "199") (name "unconnected-(PRESSURE_SENSOR_10-V_EX-Pad6)") (class "Default")
      (node (ref "PRESSURE_SENSOR_10") (pin "6") (pinfunction "V_EX_6") (pintype "bidirectional"))
    )
    (net (code "200") (name "unconnected-(PRESSURE_SENSOR_11-V1-Pad4)") (class "Default")
      (node (ref "PRESSURE_SENSOR_11") (pin "4") (pinfunction "V1_4") (pintype "bidirectional"))
    )
    (net (code "201") (name "unconnected-(PRESSURE_SENSOR_11-V2-Pad5)") (class "Default")
      (node (ref "PRESSURE_SENSOR_11") (pin "5") (pinfunction "V2_5") (pintype "bidirectional"))
    )
    (net (code "202") (name "unconnected-(PRESSURE_SENSOR_11-V_EX-Pad6)") (class "Default")
      (node (ref "PRESSURE_SENSOR_11") (pin "6") (pinfunction "V_EX_6") (pintype "bidirectional"))
    )
    (net (code "203") (name "unconnected-(PRESSURE_SENSOR_12-V1-Pad4)") (class "Default")
      (node (ref "PRESSURE_SENSOR_12") (pin "4") (pinfunction "V1_4") (pintype "bidirectional"))
    )
    (net (code "204") (name "unconnected-(PRESSURE_SENSOR_12-V2-Pad5)") (class "Default")
      (node (ref "PRESSURE_SENSOR_12") (pin "5") (pinfunction "V2_5") (pintype "bidirectional"))
    )
    (net (code "205") (name "unconnected-(PRESSURE_SENSOR_12-V_EX-Pad6)") (class "Default")
      (node (ref "PRESSURE_SENSOR_12") (pin "6") (pinfunction "V_EX_6") (pintype "bidirectional"))
    )
    (net (code "206") (name "unconnected-(PRESSURE_SENSOR_13-V1-Pad4)") (class "Default")
      (node (ref "PRESSURE_SENSOR_13") (pin "4") (pinfunction "V1_4") (pintype "bidirectional"))
    )
    (net (code "207") (name "unconnected-(PRESSURE_SENSOR_13-V2-Pad5)") (class "Default")
      (node (ref "PRESSURE_SENSOR_13") (pin "5") (pinfunction "V2_5") (pintype "bidirectional"))
    )
    (net (code "208") (name "unconnected-(PRESSURE_SENSOR_13-V_EX-Pad6)") (class "Default")
      (node (ref "PRESSURE_SENSOR_13") (pin "6") (pinfunction "V_EX_6") (pintype "bidirectional"))
    )
    (net (code "209") (name "unconnected-(PRESSURE_SENSOR_14-V1-Pad4)") (class "Default")
      (node (ref "PRESSURE_SENSOR_14") (pin "4") (pinfunction "V1_4") (pintype "bidirectional"))
    )
    (net (code "210") (name "unconnected-(PRESSURE_SENSOR_14-V2-Pad5)") (class "Default")
      (node (ref "PRESSURE_SENSOR_14") (pin "5") (pinfunction "V2_5") (pintype "bidirectional"))
    )
    (net (code "211") (name "unconnected-(PRESSURE_SENSOR_14-V_EX-Pad6)") (class "Default")
      (node (ref "PRESSURE_SENSOR_14") (pin "6") (pinfunction "V_EX_6") (pintype "bidirectional"))
    )
    (net (code "212") (name "unconnected-(PRESSURE_SENSOR_15-V1-Pad4)") (class "Default")
      (node (ref "PRESSURE_SENSOR_15") (pin "4") (pinfunction "V1_4") (pintype "bidirectional"))
    )
    (net (code "213") (name "unconnected-(PRESSURE_SENSOR_15-V2-Pad5)") (class "Default")
      (node (ref "PRESSURE_SENSOR_15") (pin "5") (pinfunction "V2_5") (pintype "bidirectional"))
    )
    (net (code "214") (name "unconnected-(PRESSURE_SENSOR_15-V_EX-Pad6)") (class "Default")
      (node (ref "PRESSURE_SENSOR_15") (pin "6") (pinfunction "V_EX_6") (pintype "bidirectional"))
    )
    (net (code "215") (name "unconnected-(PRESSURE_SENSOR_16-V1-Pad4)") (class "Default")
      (node (ref "PRESSURE_SENSOR_16") (pin "4") (pinfunction "V1_4") (pintype "bidirectional"))
    )
    (net (code "216") (name "unconnected-(PRESSURE_SENSOR_16-V2-Pad5)") (class "Default")
      (node (ref "PRESSURE_SENSOR_16") (pin "5") (pinfunction "V2_5") (pintype "bidirectional"))
    )
    (net (code "217") (name "unconnected-(PRESSURE_SENSOR_16-V_EX-Pad6)") (class "Default")
      (node (ref "PRESSURE_SENSOR_16") (pin "6") (pinfunction "V_EX_6") (pintype "bidirectional"))
    )
    (net (code "218") (name "unconnected-(PRESSURE_SENSOR_17-V1-Pad4)") (class "Default")
      (node (ref "PRESSURE_SENSOR_17") (pin "4") (pinfunction "V1_4") (pintype "bidirectional"))
    )
    (net (code "219") (name "unconnected-(PRESSURE_SENSOR_17-V2-Pad5)") (class "Default")
      (node (ref "PRESSURE_SENSOR_17") (pin "5") (pinfunction "V2_5") (pintype "bidirectional"))
    )
    (net (code "220") (name "unconnected-(PRESSURE_SENSOR_17-V_EX-Pad6)") (class "Default")
      (node (ref "PRESSURE_SENSOR_17") (pin "6") (pinfunction "V_EX_6") (pintype "bidirectional"))
    )
    (net (code "221") (name "unconnected-(PRESSURE_SENSOR_18-V1-Pad4)") (class "Default")
      (node (ref "PRESSURE_SENSOR_18") (pin "4") (pinfunction "V1_4") (pintype "bidirectional"))
    )
    (net (code "222") (name "unconnected-(PRESSURE_SENSOR_18-V2-Pad5)") (class "Default")
      (node (ref "PRESSURE_SENSOR_18") (pin "5") (pinfunction "V2_5") (pintype "bidirectional"))
    )
    (net (code "223") (name "unconnected-(PRESSURE_SENSOR_18-V_EX-Pad6)") (class "Default")
      (node (ref "PRESSURE_SENSOR_18") (pin "6") (pinfunction "V_EX_6") (pintype "bidirectional"))
    )
    (net (code "224") (name "unconnected-(PRESSURE_SENSOR_19-V1-Pad4)") (class "Default")
      (node (ref "PRESSURE_SENSOR_19") (pin "4") (pinfunction "V1_4") (pintype "bidirectional"))
    )
    (net (code "225") (name "unconnected-(PRESSURE_SENSOR_19-V2-Pad5)") (class "Default")
      (node (ref "PRESSURE_SENSOR_19") (pin "5") (pinfunction "V2_5") (pintype "bidirectional"))
    )
    (net (code "226") (name "unconnected-(PRESSURE_SENSOR_19-V_EX-Pad6)") (class "Default")
      (node (ref "PRESSURE_SENSOR_19") (pin "6") (pinfunction "V_EX_6") (pintype "bidirectional"))
    )
    (net (code "227") (name "unconnected-(PRESSURE_SENSOR_20-V1-Pad4)") (class "Default")
      (node (ref "PRESSURE_SENSOR_20") (pin "4") (pinfunction "V1_4") (pintype "bidirectional"))
    )
    (net (code "228") (name "unconnected-(PRESSURE_SENSOR_20-V2-Pad5)") (class "Default")
      (node (ref "PRESSURE_SENSOR_20") (pin "5") (pinfunction "V2_5") (pintype "bidirectional"))
    )
    (net (code "229") (name "unconnected-(PRESSURE_SENSOR_20-V_EX-Pad6)") (class "Default")
      (node (ref "PRESSURE_SENSOR_20") (pin "6") (pinfunction "V_EX_6") (pintype "bidirectional"))
    )
    (net (code "230") (name "unconnected-(PRESSURE_SENSOR_21-V1-Pad4)") (class "Default")
      (node (ref "PRESSURE_SENSOR_21") (pin "4") (pinfunction "V1_4") (pintype "bidirectional"))
    )
    (net (code "231") (name "unconnected-(PRESSURE_SENSOR_21-V2-Pad5)") (class "Default")
      (node (ref "PRESSURE_SENSOR_21") (pin "5") (pinfunction "V2_5") (pintype "bidirectional"))
    )
    (net (code "232") (name "unconnected-(PRESSURE_SENSOR_21-V_EX-Pad6)") (class "Default")
      (node (ref "PRESSURE_SENSOR_21") (pin "6") (pinfunction "V_EX_6") (pintype "bidirectional"))
    )
    (net (code "233") (name "unconnected-(PRESSURE_SENSOR_22-V1-Pad4)") (class "Default")
      (node (ref "PRESSURE_SENSOR_22") (pin "4") (pinfunction "V1_4") (pintype "bidirectional"))
    )
    (net (code "234") (name "unconnected-(PRESSURE_SENSOR_22-V2-Pad5)") (class "Default")
      (node (ref "PRESSURE_SENSOR_22") (pin "5") (pinfunction "V2_5") (pintype "bidirectional"))
    )
    (net (code "235") (name "unconnected-(PRESSURE_SENSOR_22-V_EX-Pad6)") (class "Default")
      (node (ref "PRESSURE_SENSOR_22") (pin "6") (pinfunction "V_EX_6") (pintype "bidirectional"))
    )
    (net (code "236") (name "unconnected-(PRESSURE_SENSOR_23-V1-Pad4)") (class "Default")
      (node (ref "PRESSURE_SENSOR_23") (pin "4") (pinfunction "V1_4") (pintype "bidirectional"))
    )
    (net (code "237") (name "unconnected-(PRESSURE_SENSOR_23-V2-Pad5)") (class "Default")
      (node (ref "PRESSURE_SENSOR_23") (pin "5") (pinfunction "V2_5") (pintype "bidirectional"))
    )
    (net (code "238") (name "unconnected-(PRESSURE_SENSOR_23-V_EX-Pad6)") (class "Default")
      (node (ref "PRESSURE_SENSOR_23") (pin "6") (pinfunction "V_EX_6") (pintype "bidirectional"))
    )
    (net (code "239") (name "unconnected-(PRESSURE_SENSOR_24-V1-Pad4)") (class "Default")
      (node (ref "PRESSURE_SENSOR_24") (pin "4") (pinfunction "V1_4") (pintype "bidirectional"))
    )
    (net (code "240") (name "unconnected-(PRESSURE_SENSOR_24-V2-Pad5)") (class "Default")
      (node (ref "PRESSURE_SENSOR_24") (pin "5") (pinfunction "V2_5") (pintype "bidirectional"))
    )
    (net (code "241") (name "unconnected-(PRESSURE_SENSOR_24-V_EX-Pad6)") (class "Default")
      (node (ref "PRESSURE_SENSOR_24") (pin "6") (pinfunction "V_EX_6") (pintype "bidirectional"))
    )
    (net (code "242") (name "unconnected-(SLAVE_MICRO_1-PadANG)") (class "Default")
      (node (ref "SLAVE_MICRO_1") (pin "ANG") (pinfunction "ANG_ANG") (pintype "bidirectional"))
    )
    (net (code "243") (name "unconnected-(SLAVE_MICRO_1-PadPB0)") (class "Default")
      (node (ref "SLAVE_MICRO_1") (pin "PB0") (pinfunction "PB0_PB0") (pintype "bidirectional"))
    )
    (net (code "244") (name "unconnected-(SLAVE_MICRO_1-PadPC3)") (class "Default")
      (node (ref "SLAVE_MICRO_1") (pin "PC3") (pinfunction "PC3_PC3") (pintype "bidirectional"))
    )
    (net (code "245") (name "unconnected-(SLAVE_MICRO_1-PadPC4)") (class "Default")
      (node (ref "SLAVE_MICRO_1") (pin "PC4") (pinfunction "PC4_PC4") (pintype "bidirectional"))
    )
    (net (code "246") (name "unconnected-(SLAVE_MICRO_1-PadPC5)") (class "Default")
      (node (ref "SLAVE_MICRO_1") (pin "PC5") (pinfunction "PC5_PC5") (pintype "bidirectional"))
    )
    (net (code "247") (name "unconnected-(SLAVE_MICRO_1-PadPD2)") (class "Default")
      (node (ref "SLAVE_MICRO_1") (pin "PD2") (pinfunction "PD2_PD2") (pintype "bidirectional"))
    )
    (net (code "248") (name "unconnected-(SLAVE_MICRO_1-PadPD3)") (class "Default")
      (node (ref "SLAVE_MICRO_1") (pin "PD3") (pinfunction "PD3_PD3") (pintype "bidirectional"))
    )
    (net (code "249") (name "unconnected-(SLAVE_MICRO_1-PadPD4)") (class "Default")
      (node (ref "SLAVE_MICRO_1") (pin "PD4") (pinfunction "PD4_PD4") (pintype "bidirectional"))
    )
    (net (code "250") (name "unconnected-(SLAVE_MICRO_1-PadPD5)") (class "Default")
      (node (ref "SLAVE_MICRO_1") (pin "PD5") (pinfunction "PD5_PD5") (pintype "bidirectional"))
    )
    (net (code "251") (name "unconnected-(SLAVE_MICRO_2-PadANG)") (class "Default")
      (node (ref "SLAVE_MICRO_2") (pin "ANG") (pinfunction "ANG_ANG") (pintype "bidirectional"))
    )
    (net (code "252") (name "unconnected-(SLAVE_MICRO_2-PadPB0)") (class "Default")
      (node (ref "SLAVE_MICRO_2") (pin "PB0") (pinfunction "PB0_PB0") (pintype "bidirectional"))
    )
    (net (code "253") (name "unconnected-(SLAVE_MICRO_2-PadPC3)") (class "Default")
      (node (ref "SLAVE_MICRO_2") (pin "PC3") (pinfunction "PC3_PC3") (pintype "bidirectional"))
    )
    (net (code "254") (name "unconnected-(SLAVE_MICRO_2-PadPC4)") (class "Default")
      (node (ref "SLAVE_MICRO_2") (pin "PC4") (pinfunction "PC4_PC4") (pintype "bidirectional"))
    )
    (net (code "255") (name "unconnected-(SLAVE_MICRO_2-PadPC5)") (class "Default")
      (node (ref "SLAVE_MICRO_2") (pin "PC5") (pinfunction "PC5_PC5") (pintype "bidirectional"))
    )
    (net (code "256") (name "unconnected-(SLAVE_MICRO_2-PadPD2)") (class "Default")
      (node (ref "SLAVE_MICRO_2") (pin "PD2") (pinfunction "PD2_PD2") (pintype "bidirectional"))
    )
    (net (code "257") (name "unconnected-(SLAVE_MICRO_2-PadPD3)") (class "Default")
      (node (ref "SLAVE_MICRO_2") (pin "PD3") (pinfunction "PD3_PD3") (pintype "bidirectional"))
    )
    (net (code "258") (name "unconnected-(SLAVE_MICRO_2-PadPD4)") (class "Default")
      (node (ref "SLAVE_MICRO_2") (pin "PD4") (pinfunction "PD4_PD4") (pintype "bidirectional"))
    )
    (net (code "259") (name "unconnected-(SLAVE_MICRO_2-PadPD5)") (class "Default")
      (node (ref "SLAVE_MICRO_2") (pin "PD5") (pinfunction "PD5_PD5") (pintype "bidirectional"))
    )
    (net (code "260") (name "unconnected-(SLAVE_MICRO_3-PadANG)") (class "Default")
      (node (ref "SLAVE_MICRO_3") (pin "ANG") (pinfunction "ANG_ANG") (pintype "bidirectional"))
    )
    (net (code "261") (name "unconnected-(SLAVE_MICRO_3-PadPB0)") (class "Default")
      (node (ref "SLAVE_MICRO_3") (pin "PB0") (pinfunction "PB0_PB0") (pintype "bidirectional"))
    )
    (net (code "262") (name "unconnected-(SLAVE_MICRO_3-PadPC3)") (class "Default")
      (node (ref "SLAVE_MICRO_3") (pin "PC3") (pinfunction "PC3_PC3") (pintype "bidirectional"))
    )
    (net (code "263") (name "unconnected-(SLAVE_MICRO_3-PadPC4)") (class "Default")
      (node (ref "SLAVE_MICRO_3") (pin "PC4") (pinfunction "PC4_PC4") (pintype "bidirectional"))
    )
    (net (code "264") (name "unconnected-(SLAVE_MICRO_3-PadPC5)") (class "Default")
      (node (ref "SLAVE_MICRO_3") (pin "PC5") (pinfunction "PC5_PC5") (pintype "bidirectional"))
    )
    (net (code "265") (name "unconnected-(SLAVE_MICRO_3-PadPD2)") (class "Default")
      (node (ref "SLAVE_MICRO_3") (pin "PD2") (pinfunction "PD2_PD2") (pintype "bidirectional"))
    )
    (net (code "266") (name "unconnected-(SLAVE_MICRO_3-PadPD3)") (class "Default")
      (node (ref "SLAVE_MICRO_3") (pin "PD3") (pinfunction "PD3_PD3") (pintype "bidirectional"))
    )
    (net (code "267") (name "unconnected-(SLAVE_MICRO_3-PadPD4)") (class "Default")
      (node (ref "SLAVE_MICRO_3") (pin "PD4") (pinfunction "PD4_PD4") (pintype "bidirectional"))
    )
    (net (code "268") (name "unconnected-(SLAVE_MICRO_3-PadPD5)") (class "Default")
      (node (ref "SLAVE_MICRO_3") (pin "PD5") (pinfunction "PD5_PD5") (pintype "bidirectional"))
    )
    (net (code "269") (name "unconnected-(SLAVE_MICRO_4-PadANG)") (class "Default")
      (node (ref "SLAVE_MICRO_4") (pin "ANG") (pinfunction "ANG_ANG") (pintype "bidirectional"))
    )
    (net (code "270") (name "unconnected-(SLAVE_MICRO_4-PadPB0)") (class "Default")
      (node (ref "SLAVE_MICRO_4") (pin "PB0") (pinfunction "PB0_PB0") (pintype "bidirectional"))
    )
    (net (code "271") (name "unconnected-(SLAVE_MICRO_4-PadPC3)") (class "Default")
      (node (ref "SLAVE_MICRO_4") (pin "PC3") (pinfunction "PC3_PC3") (pintype "bidirectional"))
    )
    (net (code "272") (name "unconnected-(SLAVE_MICRO_4-PadPC4)") (class "Default")
      (node (ref "SLAVE_MICRO_4") (pin "PC4") (pinfunction "PC4_PC4") (pintype "bidirectional"))
    )
    (net (code "273") (name "unconnected-(SLAVE_MICRO_4-PadPC5)") (class "Default")
      (node (ref "SLAVE_MICRO_4") (pin "PC5") (pinfunction "PC5_PC5") (pintype "bidirectional"))
    )
    (net (code "274") (name "unconnected-(SLAVE_MICRO_4-PadPD2)") (class "Default")
      (node (ref "SLAVE_MICRO_4") (pin "PD2") (pinfunction "PD2_PD2") (pintype "bidirectional"))
    )
    (net (code "275") (name "unconnected-(SLAVE_MICRO_4-PadPD3)") (class "Default")
      (node (ref "SLAVE_MICRO_4") (pin "PD3") (pinfunction "PD3_PD3") (pintype "bidirectional"))
    )
    (net (code "276") (name "unconnected-(SLAVE_MICRO_4-PadPD4)") (class "Default")
      (node (ref "SLAVE_MICRO_4") (pin "PD4") (pinfunction "PD4_PD4") (pintype "bidirectional"))
    )
    (net (code "277") (name "unconnected-(SLAVE_MICRO_4-PadPD5)") (class "Default")
      (node (ref "SLAVE_MICRO_4") (pin "PD5") (pinfunction "PD5_PD5") (pintype "bidirectional"))
    )
    (net (code "278") (name "unconnected-(SLAVE_MICRO_5-PadANG)") (class "Default")
      (node (ref "SLAVE_MICRO_5") (pin "ANG") (pinfunction "ANG_ANG") (pintype "bidirectional"))
    )
    (net (code "279") (name "unconnected-(SLAVE_MICRO_5-PadPB0)") (class "Default")
      (node (ref "SLAVE_MICRO_5") (pin "PB0") (pinfunction "PB0_PB0") (pintype "bidirectional"))
    )
    (net (code "280") (name "unconnected-(SLAVE_MICRO_5-PadPC3)") (class "Default")
      (node (ref "SLAVE_MICRO_5") (pin "PC3") (pinfunction "PC3_PC3") (pintype "bidirectional"))
    )
    (net (code "281") (name "unconnected-(SLAVE_MICRO_5-PadPC4)") (class "Default")
      (node (ref "SLAVE_MICRO_5") (pin "PC4") (pinfunction "PC4_PC4") (pintype "bidirectional"))
    )
    (net (code "282") (name "unconnected-(SLAVE_MICRO_5-PadPC5)") (class "Default")
      (node (ref "SLAVE_MICRO_5") (pin "PC5") (pinfunction "PC5_PC5") (pintype "bidirectional"))
    )
    (net (code "283") (name "unconnected-(SLAVE_MICRO_5-PadPD2)") (class "Default")
      (node (ref "SLAVE_MICRO_5") (pin "PD2") (pinfunction "PD2_PD2") (pintype "bidirectional"))
    )
    (net (code "284") (name "unconnected-(SLAVE_MICRO_5-PadPD3)") (class "Default")
      (node (ref "SLAVE_MICRO_5") (pin "PD3") (pinfunction "PD3_PD3") (pintype "bidirectional"))
    )
    (net (code "285") (name "unconnected-(SLAVE_MICRO_5-PadPD4)") (class "Default")
      (node (ref "SLAVE_MICRO_5") (pin "PD4") (pinfunction "PD4_PD4") (pintype "bidirectional"))
    )
    (net (code "286") (name "unconnected-(SLAVE_MICRO_5-PadPD5)") (class "Default")
      (node (ref "SLAVE_MICRO_5") (pin "PD5") (pinfunction "PD5_PD5") (pintype "bidirectional"))
    )
    (net (code "287") (name "unconnected-(SLAVE_MICRO_6-PadANG)") (class "Default")
      (node (ref "SLAVE_MICRO_6") (pin "ANG") (pinfunction "ANG_ANG") (pintype "bidirectional"))
    )
    (net (code "288") (name "unconnected-(SLAVE_MICRO_6-PadPB0)") (class "Default")
      (node (ref "SLAVE_MICRO_6") (pin "PB0") (pinfunction "PB0_PB0") (pintype "bidirectional"))
    )
    (net (code "289") (name "unconnected-(SLAVE_MICRO_6-PadPC3)") (class "Default")
      (node (ref "SLAVE_MICRO_6") (pin "PC3") (pinfunction "PC3_PC3") (pintype "bidirectional"))
    )
    (net (code "290") (name "unconnected-(SLAVE_MICRO_6-PadPC4)") (class "Default")
      (node (ref "SLAVE_MICRO_6") (pin "PC4") (pinfunction "PC4_PC4") (pintype "bidirectional"))
    )
    (net (code "291") (name "unconnected-(SLAVE_MICRO_6-PadPC5)") (class "Default")
      (node (ref "SLAVE_MICRO_6") (pin "PC5") (pinfunction "PC5_PC5") (pintype "bidirectional"))
    )
    (net (code "292") (name "unconnected-(SLAVE_MICRO_6-PadPD2)") (class "Default")
      (node (ref "SLAVE_MICRO_6") (pin "PD2") (pinfunction "PD2_PD2") (pintype "bidirectional"))
    )
    (net (code "293") (name "unconnected-(SLAVE_MICRO_6-PadPD3)") (class "Default")
      (node (ref "SLAVE_MICRO_6") (pin "PD3") (pinfunction "PD3_PD3") (pintype "bidirectional"))
    )
    (net (code "294") (name "unconnected-(SLAVE_MICRO_6-PadPD4)") (class "Default")
      (node (ref "SLAVE_MICRO_6") (pin "PD4") (pinfunction "PD4_PD4") (pintype "bidirectional"))
    )
    (net (code "295") (name "unconnected-(SLAVE_MICRO_6-PadPD5)") (class "Default")
      (node (ref "SLAVE_MICRO_6") (pin "PD5") (pinfunction "PD5_PD5") (pintype "bidirectional"))
    )
    (net (code "296") (name "unconnected-(SLAVE_MICRO_7-PadANG)") (class "Default")
      (node (ref "SLAVE_MICRO_7") (pin "ANG") (pinfunction "ANG_ANG") (pintype "bidirectional"))
    )
    (net (code "297") (name "unconnected-(SLAVE_MICRO_7-PadPB0)") (class "Default")
      (node (ref "SLAVE_MICRO_7") (pin "PB0") (pinfunction "PB0_PB0") (pintype "bidirectional"))
    )
    (net (code "298") (name "unconnected-(SLAVE_MICRO_7-PadPC3)") (class "Default")
      (node (ref "SLAVE_MICRO_7") (pin "PC3") (pinfunction "PC3_PC3") (pintype "bidirectional"))
    )
    (net (code "299") (name "unconnected-(SLAVE_MICRO_7-PadPC4)") (class "Default")
      (node (ref "SLAVE_MICRO_7") (pin "PC4") (pinfunction "PC4_PC4") (pintype "bidirectional"))
    )
    (net (code "300") (name "unconnected-(SLAVE_MICRO_7-PadPC5)") (class "Default")
      (node (ref "SLAVE_MICRO_7") (pin "PC5") (pinfunction "PC5_PC5") (pintype "bidirectional"))
    )
    (net (code "301") (name "unconnected-(SLAVE_MICRO_7-PadPD2)") (class "Default")
      (node (ref "SLAVE_MICRO_7") (pin "PD2") (pinfunction "PD2_PD2") (pintype "bidirectional"))
    )
    (net (code "302") (name "unconnected-(SLAVE_MICRO_7-PadPD3)") (class "Default")
      (node (ref "SLAVE_MICRO_7") (pin "PD3") (pinfunction "PD3_PD3") (pintype "bidirectional"))
    )
    (net (code "303") (name "unconnected-(SLAVE_MICRO_7-PadPD4)") (class "Default")
      (node (ref "SLAVE_MICRO_7") (pin "PD4") (pinfunction "PD4_PD4") (pintype "bidirectional"))
    )
    (net (code "304") (name "unconnected-(SLAVE_MICRO_7-PadPD5)") (class "Default")
      (node (ref "SLAVE_MICRO_7") (pin "PD5") (pinfunction "PD5_PD5") (pintype "bidirectional"))
    )
    (net (code "305") (name "unconnected-(SLAVE_MICRO_8-PadANG)") (class "Default")
      (node (ref "SLAVE_MICRO_8") (pin "ANG") (pinfunction "ANG_ANG") (pintype "bidirectional"))
    )
    (net (code "306") (name "unconnected-(SLAVE_MICRO_8-PadPB0)") (class "Default")
      (node (ref "SLAVE_MICRO_8") (pin "PB0") (pinfunction "PB0_PB0") (pintype "bidirectional"))
    )
    (net (code "307") (name "unconnected-(SLAVE_MICRO_8-PadPC3)") (class "Default")
      (node (ref "SLAVE_MICRO_8") (pin "PC3") (pinfunction "PC3_PC3") (pintype "bidirectional"))
    )
    (net (code "308") (name "unconnected-(SLAVE_MICRO_8-PadPC4)") (class "Default")
      (node (ref "SLAVE_MICRO_8") (pin "PC4") (pinfunction "PC4_PC4") (pintype "bidirectional"))
    )
    (net (code "309") (name "unconnected-(SLAVE_MICRO_8-PadPC5)") (class "Default")
      (node (ref "SLAVE_MICRO_8") (pin "PC5") (pinfunction "PC5_PC5") (pintype "bidirectional"))
    )
    (net (code "310") (name "unconnected-(SLAVE_MICRO_8-PadPD2)") (class "Default")
      (node (ref "SLAVE_MICRO_8") (pin "PD2") (pinfunction "PD2_PD2") (pintype "bidirectional"))
    )
    (net (code "311") (name "unconnected-(SLAVE_MICRO_8-PadPD3)") (class "Default")
      (node (ref "SLAVE_MICRO_8") (pin "PD3") (pinfunction "PD3_PD3") (pintype "bidirectional"))
    )
    (net (code "312") (name "unconnected-(SLAVE_MICRO_8-PadPD4)") (class "Default")
      (node (ref "SLAVE_MICRO_8") (pin "PD4") (pinfunction "PD4_PD4") (pintype "bidirectional"))
    )
    (net (code "313") (name "unconnected-(SLAVE_MICRO_8-PadPD5)") (class "Default")
      (node (ref "SLAVE_MICRO_8") (pin "PD5") (pinfunction "PD5_PD5") (pintype "bidirectional"))
    )
    (net (code "314") (name "unconnected-(SLAVE_MICRO_9-PadANG)") (class "Default")
      (node (ref "SLAVE_MICRO_9") (pin "ANG") (pinfunction "ANG_ANG") (pintype "bidirectional"))
    )
    (net (code "315") (name "unconnected-(SLAVE_MICRO_9-PadPB0)") (class "Default")
      (node (ref "SLAVE_MICRO_9") (pin "PB0") (pinfunction "PB0_PB0") (pintype "bidirectional"))
    )
    (net (code "316") (name "unconnected-(SLAVE_MICRO_9-PadPC3)") (class "Default")
      (node (ref "SLAVE_MICRO_9") (pin "PC3") (pinfunction "PC3_PC3") (pintype "bidirectional"))
    )
    (net (code "317") (name "unconnected-(SLAVE_MICRO_9-PadPC4)") (class "Default")
      (node (ref "SLAVE_MICRO_9") (pin "PC4") (pinfunction "PC4_PC4") (pintype "bidirectional"))
    )
    (net (code "318") (name "unconnected-(SLAVE_MICRO_9-PadPC5)") (class "Default")
      (node (ref "SLAVE_MICRO_9") (pin "PC5") (pinfunction "PC5_PC5") (pintype "bidirectional"))
    )
    (net (code "319") (name "unconnected-(SLAVE_MICRO_9-PadPD2)") (class "Default")
      (node (ref "SLAVE_MICRO_9") (pin "PD2") (pinfunction "PD2_PD2") (pintype "bidirectional"))
    )
    (net (code "320") (name "unconnected-(SLAVE_MICRO_9-PadPD3)") (class "Default")
      (node (ref "SLAVE_MICRO_9") (pin "PD3") (pinfunction "PD3_PD3") (pintype "bidirectional"))
    )
    (net (code "321") (name "unconnected-(SLAVE_MICRO_9-PadPD4)") (class "Default")
      (node (ref "SLAVE_MICRO_9") (pin "PD4") (pinfunction "PD4_PD4") (pintype "bidirectional"))
    )
    (net (code "322") (name "unconnected-(SLAVE_MICRO_9-PadPD5)") (class "Default")
      (node (ref "SLAVE_MICRO_9") (pin "PD5") (pinfunction "PD5_PD5") (pintype "bidirectional"))
    )
    (net (code "323") (name "unconnected-(SLAVE_MICRO_10-PadANG)") (class "Default")
      (node (ref "SLAVE_MICRO_10") (pin "ANG") (pinfunction "ANG_ANG") (pintype "bidirectional"))
    )
    (net (code "324") (name "unconnected-(SLAVE_MICRO_10-PadPB0)") (class "Default")
      (node (ref "SLAVE_MICRO_10") (pin "PB0") (pinfunction "PB0_PB0") (pintype "bidirectional"))
    )
    (net (code "325") (name "unconnected-(SLAVE_MICRO_10-PadPC3)") (class "Default")
      (node (ref "SLAVE_MICRO_10") (pin "PC3") (pinfunction "PC3_PC3") (pintype "bidirectional"))
    )
    (net (code "326") (name "unconnected-(SLAVE_MICRO_10-PadPC4)") (class "Default")
      (node (ref "SLAVE_MICRO_10") (pin "PC4") (pinfunction "PC4_PC4") (pintype "bidirectional"))
    )
    (net (code "327") (name "unconnected-(SLAVE_MICRO_10-PadPC5)") (class "Default")
      (node (ref "SLAVE_MICRO_10") (pin "PC5") (pinfunction "PC5_PC5") (pintype "bidirectional"))
    )
    (net (code "328") (name "unconnected-(SLAVE_MICRO_10-PadPD2)") (class "Default")
      (node (ref "SLAVE_MICRO_10") (pin "PD2") (pinfunction "PD2_PD2") (pintype "bidirectional"))
    )
    (net (code "329") (name "unconnected-(SLAVE_MICRO_10-PadPD3)") (class "Default")
      (node (ref "SLAVE_MICRO_10") (pin "PD3") (pinfunction "PD3_PD3") (pintype "bidirectional"))
    )
    (net (code "330") (name "unconnected-(SLAVE_MICRO_10-PadPD4)") (class "Default")
      (node (ref "SLAVE_MICRO_10") (pin "PD4") (pinfunction "PD4_PD4") (pintype "bidirectional"))
    )
    (net (code "331") (name "unconnected-(SLAVE_MICRO_10-PadPD5)") (class "Default")
      (node (ref "SLAVE_MICRO_10") (pin "PD5") (pinfunction "PD5_PD5") (pintype "bidirectional"))
    )
    (net (code "332") (name "unconnected-(SLAVE_MICRO_11-PadANG)") (class "Default")
      (node (ref "SLAVE_MICRO_11") (pin "ANG") (pinfunction "ANG_ANG") (pintype "bidirectional"))
    )
    (net (code "333") (name "unconnected-(SLAVE_MICRO_11-PadPB0)") (class "Default")
      (node (ref "SLAVE_MICRO_11") (pin "PB0") (pinfunction "PB0_PB0") (pintype "bidirectional"))
    )
    (net (code "334") (name "unconnected-(SLAVE_MICRO_11-PadPC3)") (class "Default")
      (node (ref "SLAVE_MICRO_11") (pin "PC3") (pinfunction "PC3_PC3") (pintype "bidirectional"))
    )
    (net (code "335") (name "unconnected-(SLAVE_MICRO_11-PadPC4)") (class "Default")
      (node (ref "SLAVE_MICRO_11") (pin "PC4") (pinfunction "PC4_PC4") (pintype "bidirectional"))
    )
    (net (code "336") (name "unconnected-(SLAVE_MICRO_11-PadPC5)") (class "Default")
      (node (ref "SLAVE_MICRO_11") (pin "PC5") (pinfunction "PC5_PC5") (pintype "bidirectional"))
    )
    (net (code "337") (name "unconnected-(SLAVE_MICRO_11-PadPD2)") (class "Default")
      (node (ref "SLAVE_MICRO_11") (pin "PD2") (pinfunction "PD2_PD2") (pintype "bidirectional"))
    )
    (net (code "338") (name "unconnected-(SLAVE_MICRO_11-PadPD3)") (class "Default")
      (node (ref "SLAVE_MICRO_11") (pin "PD3") (pinfunction "PD3_PD3") (pintype "bidirectional"))
    )
    (net (code "339") (name "unconnected-(SLAVE_MICRO_11-PadPD4)") (class "Default")
      (node (ref "SLAVE_MICRO_11") (pin "PD4") (pinfunction "PD4_PD4") (pintype "bidirectional"))
    )
    (net (code "340") (name "unconnected-(SLAVE_MICRO_11-PadPD5)") (class "Default")
      (node (ref "SLAVE_MICRO_11") (pin "PD5") (pinfunction "PD5_PD5") (pintype "bidirectional"))
    )
    (net (code "341") (name "unconnected-(SLAVE_MICRO_12-PadANG)") (class "Default")
      (node (ref "SLAVE_MICRO_12") (pin "ANG") (pinfunction "ANG_ANG") (pintype "bidirectional"))
    )
    (net (code "342") (name "unconnected-(SLAVE_MICRO_12-PadPB0)") (class "Default")
      (node (ref "SLAVE_MICRO_12") (pin "PB0") (pinfunction "PB0_PB0") (pintype "bidirectional"))
    )
    (net (code "343") (name "unconnected-(SLAVE_MICRO_12-PadPC3)") (class "Default")
      (node (ref "SLAVE_MICRO_12") (pin "PC3") (pinfunction "PC3_PC3") (pintype "bidirectional"))
    )
    (net (code "344") (name "unconnected-(SLAVE_MICRO_12-PadPC4)") (class "Default")
      (node (ref "SLAVE_MICRO_12") (pin "PC4") (pinfunction "PC4_PC4") (pintype "bidirectional"))
    )
    (net (code "345") (name "unconnected-(SLAVE_MICRO_12-PadPC5)") (class "Default")
      (node (ref "SLAVE_MICRO_12") (pin "PC5") (pinfunction "PC5_PC5") (pintype "bidirectional"))
    )
    (net (code "346") (name "unconnected-(SLAVE_MICRO_12-PadPD2)") (class "Default")
      (node (ref "SLAVE_MICRO_12") (pin "PD2") (pinfunction "PD2_PD2") (pintype "bidirectional"))
    )
    (net (code "347") (name "unconnected-(SLAVE_MICRO_12-PadPD3)") (class "Default")
      (node (ref "SLAVE_MICRO_12") (pin "PD3") (pinfunction "PD3_PD3") (pintype "bidirectional"))
    )
    (net (code "348") (name "unconnected-(SLAVE_MICRO_12-PadPD4)") (class "Default")
      (node (ref "SLAVE_MICRO_12") (pin "PD4") (pinfunction "PD4_PD4") (pintype "bidirectional"))
    )
    (net (code "349") (name "unconnected-(SLAVE_MICRO_12-PadPD5)") (class "Default")
      (node (ref "SLAVE_MICRO_12") (pin "PD5") (pinfunction "PD5_PD5") (pintype "bidirectional"))
    )
    (net (code "350") (name "unconnected-(SLAVE_MICRO_13-PadANG)") (class "Default")
      (node (ref "SLAVE_MICRO_13") (pin "ANG") (pinfunction "ANG_ANG") (pintype "bidirectional"))
    )
    (net (code "351") (name "unconnected-(SLAVE_MICRO_13-PadPB0)") (class "Default")
      (node (ref "SLAVE_MICRO_13") (pin "PB0") (pinfunction "PB0_PB0") (pintype "bidirectional"))
    )
    (net (code "352") (name "unconnected-(SLAVE_MICRO_13-PadPC3)") (class "Default")
      (node (ref "SLAVE_MICRO_13") (pin "PC3") (pinfunction "PC3_PC3") (pintype "bidirectional"))
    )
    (net (code "353") (name "unconnected-(SLAVE_MICRO_13-PadPC4)") (class "Default")
      (node (ref "SLAVE_MICRO_13") (pin "PC4") (pinfunction "PC4_PC4") (pintype "bidirectional"))
    )
    (net (code "354") (name "unconnected-(SLAVE_MICRO_13-PadPC5)") (class "Default")
      (node (ref "SLAVE_MICRO_13") (pin "PC5") (pinfunction "PC5_PC5") (pintype "bidirectional"))
    )
    (net (code "355") (name "unconnected-(SLAVE_MICRO_13-PadPD2)") (class "Default")
      (node (ref "SLAVE_MICRO_13") (pin "PD2") (pinfunction "PD2_PD2") (pintype "bidirectional"))
    )
    (net (code "356") (name "unconnected-(SLAVE_MICRO_13-PadPD3)") (class "Default")
      (node (ref "SLAVE_MICRO_13") (pin "PD3") (pinfunction "PD3_PD3") (pintype "bidirectional"))
    )
    (net (code "357") (name "unconnected-(SLAVE_MICRO_13-PadPD4)") (class "Default")
      (node (ref "SLAVE_MICRO_13") (pin "PD4") (pinfunction "PD4_PD4") (pintype "bidirectional"))
    )
    (net (code "358") (name "unconnected-(SLAVE_MICRO_13-PadPD5)") (class "Default")
      (node (ref "SLAVE_MICRO_13") (pin "PD5") (pinfunction "PD5_PD5") (pintype "bidirectional"))
    )
    (net (code "359") (name "unconnected-(SLAVE_MICRO_14-PadANG)") (class "Default")
      (node (ref "SLAVE_MICRO_14") (pin "ANG") (pinfunction "ANG_ANG") (pintype "bidirectional"))
    )
    (net (code "360") (name "unconnected-(SLAVE_MICRO_14-PadPB0)") (class "Default")
      (node (ref "SLAVE_MICRO_14") (pin "PB0") (pinfunction "PB0_PB0") (pintype "bidirectional"))
    )
    (net (code "361") (name "unconnected-(SLAVE_MICRO_14-PadPC3)") (class "Default")
      (node (ref "SLAVE_MICRO_14") (pin "PC3") (pinfunction "PC3_PC3") (pintype "bidirectional"))
    )
    (net (code "362") (name "unconnected-(SLAVE_MICRO_14-PadPC4)") (class "Default")
      (node (ref "SLAVE_MICRO_14") (pin "PC4") (pinfunction "PC4_PC4") (pintype "bidirectional"))
    )
    (net (code "363") (name "unconnected-(SLAVE_MICRO_14-PadPC5)") (class "Default")
      (node (ref "SLAVE_MICRO_14") (pin "PC5") (pinfunction "PC5_PC5") (pintype "bidirectional"))
    )
    (net (code "364") (name "unconnected-(SLAVE_MICRO_14-PadPD2)") (class "Default")
      (node (ref "SLAVE_MICRO_14") (pin "PD2") (pinfunction "PD2_PD2") (pintype "bidirectional"))
    )
    (net (code "365") (name "unconnected-(SLAVE_MICRO_14-PadPD3)") (class "Default")
      (node (ref "SLAVE_MICRO_14") (pin "PD3") (pinfunction "PD3_PD3") (pintype "bidirectional"))
    )
    (net (code "366") (name "unconnected-(SLAVE_MICRO_14-PadPD4)") (class "Default")
      (node (ref "SLAVE_MICRO_14") (pin "PD4") (pinfunction "PD4_PD4") (pintype "bidirectional"))
    )
    (net (code "367") (name "unconnected-(SLAVE_MICRO_14-PadPD5)") (class "Default")
      (node (ref "SLAVE_MICRO_14") (pin "PD5") (pinfunction "PD5_PD5") (pintype "bidirectional"))
    )
    (net (code "368") (name "unconnected-(SLAVE_MICRO_15-PadANG)") (class "Default")
      (node (ref "SLAVE_MICRO_15") (pin "ANG") (pinfunction "ANG_ANG") (pintype "bidirectional"))
    )
    (net (code "369") (name "unconnected-(SLAVE_MICRO_15-PadPB0)") (class "Default")
      (node (ref "SLAVE_MICRO_15") (pin "PB0") (pinfunction "PB0_PB0") (pintype "bidirectional"))
    )
    (net (code "370") (name "unconnected-(SLAVE_MICRO_15-PadPC3)") (class "Default")
      (node (ref "SLAVE_MICRO_15") (pin "PC3") (pinfunction "PC3_PC3") (pintype "bidirectional"))
    )
    (net (code "371") (name "unconnected-(SLAVE_MICRO_15-PadPC4)") (class "Default")
      (node (ref "SLAVE_MICRO_15") (pin "PC4") (pinfunction "PC4_PC4") (pintype "bidirectional"))
    )
    (net (code "372") (name "unconnected-(SLAVE_MICRO_15-PadPC5)") (class "Default")
      (node (ref "SLAVE_MICRO_15") (pin "PC5") (pinfunction "PC5_PC5") (pintype "bidirectional"))
    )
    (net (code "373") (name "unconnected-(SLAVE_MICRO_15-PadPD2)") (class "Default")
      (node (ref "SLAVE_MICRO_15") (pin "PD2") (pinfunction "PD2_PD2") (pintype "bidirectional"))
    )
    (net (code "374") (name "unconnected-(SLAVE_MICRO_15-PadPD3)") (class "Default")
      (node (ref "SLAVE_MICRO_15") (pin "PD3") (pinfunction "PD3_PD3") (pintype "bidirectional"))
    )
    (net (code "375") (name "unconnected-(SLAVE_MICRO_15-PadPD4)") (class "Default")
      (node (ref "SLAVE_MICRO_15") (pin "PD4") (pinfunction "PD4_PD4") (pintype "bidirectional"))
    )
    (net (code "376") (name "unconnected-(SLAVE_MICRO_15-PadPD5)") (class "Default")
      (node (ref "SLAVE_MICRO_15") (pin "PD5") (pinfunction "PD5_PD5") (pintype "bidirectional"))
    )
    (net (code "377") (name "unconnected-(SLAVE_MICRO_16-PadANG)") (class "Default")
      (node (ref "SLAVE_MICRO_16") (pin "ANG") (pinfunction "ANG_ANG") (pintype "bidirectional"))
    )
    (net (code "378") (name "unconnected-(SLAVE_MICRO_16-PadPB0)") (class "Default")
      (node (ref "SLAVE_MICRO_16") (pin "PB0") (pinfunction "PB0_PB0") (pintype "bidirectional"))
    )
    (net (code "379") (name "unconnected-(SLAVE_MICRO_16-PadPC3)") (class "Default")
      (node (ref "SLAVE_MICRO_16") (pin "PC3") (pinfunction "PC3_PC3") (pintype "bidirectional"))
    )
    (net (code "380") (name "unconnected-(SLAVE_MICRO_16-PadPC4)") (class "Default")
      (node (ref "SLAVE_MICRO_16") (pin "PC4") (pinfunction "PC4_PC4") (pintype "bidirectional"))
    )
    (net (code "381") (name "unconnected-(SLAVE_MICRO_16-PadPC5)") (class "Default")
      (node (ref "SLAVE_MICRO_16") (pin "PC5") (pinfunction "PC5_PC5") (pintype "bidirectional"))
    )
    (net (code "382") (name "unconnected-(SLAVE_MICRO_16-PadPD2)") (class "Default")
      (node (ref "SLAVE_MICRO_16") (pin "PD2") (pinfunction "PD2_PD2") (pintype "bidirectional"))
    )
    (net (code "383") (name "unconnected-(SLAVE_MICRO_16-PadPD3)") (class "Default")
      (node (ref "SLAVE_MICRO_16") (pin "PD3") (pinfunction "PD3_PD3") (pintype "bidirectional"))
    )
    (net (code "384") (name "unconnected-(SLAVE_MICRO_16-PadPD4)") (class "Default")
      (node (ref "SLAVE_MICRO_16") (pin "PD4") (pinfunction "PD4_PD4") (pintype "bidirectional"))
    )
    (net (code "385") (name "unconnected-(SLAVE_MICRO_16-PadPD5)") (class "Default")
      (node (ref "SLAVE_MICRO_16") (pin "PD5") (pinfunction "PD5_PD5") (pintype "bidirectional"))
    )
    (net (code "386") (name "unconnected-(SLAVE_MICRO_17-PadANG)") (class "Default")
      (node (ref "SLAVE_MICRO_17") (pin "ANG") (pinfunction "ANG_ANG") (pintype "bidirectional"))
    )
    (net (code "387") (name "unconnected-(SLAVE_MICRO_17-PadPB0)") (class "Default")
      (node (ref "SLAVE_MICRO_17") (pin "PB0") (pinfunction "PB0_PB0") (pintype "bidirectional"))
    )
    (net (code "388") (name "unconnected-(SLAVE_MICRO_17-PadPC3)") (class "Default")
      (node (ref "SLAVE_MICRO_17") (pin "PC3") (pinfunction "PC3_PC3") (pintype "bidirectional"))
    )
    (net (code "389") (name "unconnected-(SLAVE_MICRO_17-PadPC4)") (class "Default")
      (node (ref "SLAVE_MICRO_17") (pin "PC4") (pinfunction "PC4_PC4") (pintype "bidirectional"))
    )
    (net (code "390") (name "unconnected-(SLAVE_MICRO_17-PadPC5)") (class "Default")
      (node (ref "SLAVE_MICRO_17") (pin "PC5") (pinfunction "PC5_PC5") (pintype "bidirectional"))
    )
    (net (code "391") (name "unconnected-(SLAVE_MICRO_17-PadPD2)") (class "Default")
      (node (ref "SLAVE_MICRO_17") (pin "PD2") (pinfunction "PD2_PD2") (pintype "bidirectional"))
    )
    (net (code "392") (name "unconnected-(SLAVE_MICRO_17-PadPD3)") (class "Default")
      (node (ref "SLAVE_MICRO_17") (pin "PD3") (pinfunction "PD3_PD3") (pintype "bidirectional"))
    )
    (net (code "393") (name "unconnected-(SLAVE_MICRO_17-PadPD4)") (class "Default")
      (node (ref "SLAVE_MICRO_17") (pin "PD4") (pinfunction "PD4_PD4") (pintype "bidirectional"))
    )
    (net (code "394") (name "unconnected-(SLAVE_MICRO_17-PadPD5)") (class "Default")
      (node (ref "SLAVE_MICRO_17") (pin "PD5") (pinfunction "PD5_PD5") (pintype "bidirectional"))
    )
    (net (code "395") (name "unconnected-(SLAVE_MICRO_18-PadANG)") (class "Default")
      (node (ref "SLAVE_MICRO_18") (pin "ANG") (pinfunction "ANG_ANG") (pintype "bidirectional"))
    )
    (net (code "396") (name "unconnected-(SLAVE_MICRO_18-PadPB0)") (class "Default")
      (node (ref "SLAVE_MICRO_18") (pin "PB0") (pinfunction "PB0_PB0") (pintype "bidirectional"))
    )
    (net (code "397") (name "unconnected-(SLAVE_MICRO_18-PadPC3)") (class "Default")
      (node (ref "SLAVE_MICRO_18") (pin "PC3") (pinfunction "PC3_PC3") (pintype "bidirectional"))
    )
    (net (code "398") (name "unconnected-(SLAVE_MICRO_18-PadPC4)") (class "Default")
      (node (ref "SLAVE_MICRO_18") (pin "PC4") (pinfunction "PC4_PC4") (pintype "bidirectional"))
    )
    (net (code "399") (name "unconnected-(SLAVE_MICRO_18-PadPC5)") (class "Default")
      (node (ref "SLAVE_MICRO_18") (pin "PC5") (pinfunction "PC5_PC5") (pintype "bidirectional"))
    )
    (net (code "400") (name "unconnected-(SLAVE_MICRO_18-PadPD2)") (class "Default")
      (node (ref "SLAVE_MICRO_18") (pin "PD2") (pinfunction "PD2_PD2") (pintype "bidirectional"))
    )
    (net (code "401") (name "unconnected-(SLAVE_MICRO_18-PadPD3)") (class "Default")
      (node (ref "SLAVE_MICRO_18") (pin "PD3") (pinfunction "PD3_PD3") (pintype "bidirectional"))
    )
    (net (code "402") (name "unconnected-(SLAVE_MICRO_18-PadPD4)") (class "Default")
      (node (ref "SLAVE_MICRO_18") (pin "PD4") (pinfunction "PD4_PD4") (pintype "bidirectional"))
    )
    (net (code "403") (name "unconnected-(SLAVE_MICRO_18-PadPD5)") (class "Default")
      (node (ref "SLAVE_MICRO_18") (pin "PD5") (pinfunction "PD5_PD5") (pintype "bidirectional"))
    )
    (net (code "404") (name "unconnected-(SLAVE_MICRO_19-PadANG)") (class "Default")
      (node (ref "SLAVE_MICRO_19") (pin "ANG") (pinfunction "ANG_ANG") (pintype "bidirectional"))
    )
    (net (code "405") (name "unconnected-(SLAVE_MICRO_19-PadPB0)") (class "Default")
      (node (ref "SLAVE_MICRO_19") (pin "PB0") (pinfunction "PB0_PB0") (pintype "bidirectional"))
    )
    (net (code "406") (name "unconnected-(SLAVE_MICRO_19-PadPC3)") (class "Default")
      (node (ref "SLAVE_MICRO_19") (pin "PC3") (pinfunction "PC3_PC3") (pintype "bidirectional"))
    )
    (net (code "407") (name "unconnected-(SLAVE_MICRO_19-PadPC4)") (class "Default")
      (node (ref "SLAVE_MICRO_19") (pin "PC4") (pinfunction "PC4_PC4") (pintype "bidirectional"))
    )
    (net (code "408") (name "unconnected-(SLAVE_MICRO_19-PadPC5)") (class "Default")
      (node (ref "SLAVE_MICRO_19") (pin "PC5") (pinfunction "PC5_PC5") (pintype "bidirectional"))
    )
    (net (code "409") (name "unconnected-(SLAVE_MICRO_19-PadPD2)") (class "Default")
      (node (ref "SLAVE_MICRO_19") (pin "PD2") (pinfunction "PD2_PD2") (pintype "bidirectional"))
    )
    (net (code "410") (name "unconnected-(SLAVE_MICRO_19-PadPD3)") (class "Default")
      (node (ref "SLAVE_MICRO_19") (pin "PD3") (pinfunction "PD3_PD3") (pintype "bidirectional"))
    )
    (net (code "411") (name "unconnected-(SLAVE_MICRO_19-PadPD4)") (class "Default")
      (node (ref "SLAVE_MICRO_19") (pin "PD4") (pinfunction "PD4_PD4") (pintype "bidirectional"))
    )
    (net (code "412") (name "unconnected-(SLAVE_MICRO_19-PadPD5)") (class "Default")
      (node (ref "SLAVE_MICRO_19") (pin "PD5") (pinfunction "PD5_PD5") (pintype "bidirectional"))
    )
    (net (code "413") (name "unconnected-(SLAVE_MICRO_20-PadANG)") (class "Default")
      (node (ref "SLAVE_MICRO_20") (pin "ANG") (pinfunction "ANG_ANG") (pintype "bidirectional"))
    )
    (net (code "414") (name "unconnected-(SLAVE_MICRO_20-PadPB0)") (class "Default")
      (node (ref "SLAVE_MICRO_20") (pin "PB0") (pinfunction "PB0_PB0") (pintype "bidirectional"))
    )
    (net (code "415") (name "unconnected-(SLAVE_MICRO_20-PadPC3)") (class "Default")
      (node (ref "SLAVE_MICRO_20") (pin "PC3") (pinfunction "PC3_PC3") (pintype "bidirectional"))
    )
    (net (code "416") (name "unconnected-(SLAVE_MICRO_20-PadPC4)") (class "Default")
      (node (ref "SLAVE_MICRO_20") (pin "PC4") (pinfunction "PC4_PC4") (pintype "bidirectional"))
    )
    (net (code "417") (name "unconnected-(SLAVE_MICRO_20-PadPC5)") (class "Default")
      (node (ref "SLAVE_MICRO_20") (pin "PC5") (pinfunction "PC5_PC5") (pintype "bidirectional"))
    )
    (net (code "418") (name "unconnected-(SLAVE_MICRO_20-PadPD2)") (class "Default")
      (node (ref "SLAVE_MICRO_20") (pin "PD2") (pinfunction "PD2_PD2") (pintype "bidirectional"))
    )
    (net (code "419") (name "unconnected-(SLAVE_MICRO_20-PadPD3)") (class "Default")
      (node (ref "SLAVE_MICRO_20") (pin "PD3") (pinfunction "PD3_PD3") (pintype "bidirectional"))
    )
    (net (code "420") (name "unconnected-(SLAVE_MICRO_20-PadPD4)") (class "Default")
      (node (ref "SLAVE_MICRO_20") (pin "PD4") (pinfunction "PD4_PD4") (pintype "bidirectional"))
    )
    (net (code "421") (name "unconnected-(SLAVE_MICRO_20-PadPD5)") (class "Default")
      (node (ref "SLAVE_MICRO_20") (pin "PD5") (pinfunction "PD5_PD5") (pintype "bidirectional"))
    )
    (net (code "422") (name "unconnected-(SLAVE_MICRO_21-PadANG)") (class "Default")
      (node (ref "SLAVE_MICRO_21") (pin "ANG") (pinfunction "ANG_ANG") (pintype "bidirectional"))
    )
    (net (code "423") (name "unconnected-(SLAVE_MICRO_21-PadPB0)") (class "Default")
      (node (ref "SLAVE_MICRO_21") (pin "PB0") (pinfunction "PB0_PB0") (pintype "bidirectional"))
    )
    (net (code "424") (name "unconnected-(SLAVE_MICRO_21-PadPC3)") (class "Default")
      (node (ref "SLAVE_MICRO_21") (pin "PC3") (pinfunction "PC3_PC3") (pintype "bidirectional"))
    )
    (net (code "425") (name "unconnected-(SLAVE_MICRO_21-PadPC4)") (class "Default")
      (node (ref "SLAVE_MICRO_21") (pin "PC4") (pinfunction "PC4_PC4") (pintype "bidirectional"))
    )
    (net (code "426") (name "unconnected-(SLAVE_MICRO_21-PadPC5)") (class "Default")
      (node (ref "SLAVE_MICRO_21") (pin "PC5") (pinfunction "PC5_PC5") (pintype "bidirectional"))
    )
    (net (code "427") (name "unconnected-(SLAVE_MICRO_21-PadPD2)") (class "Default")
      (node (ref "SLAVE_MICRO_21") (pin "PD2") (pinfunction "PD2_PD2") (pintype "bidirectional"))
    )
    (net (code "428") (name "unconnected-(SLAVE_MICRO_21-PadPD3)") (class "Default")
      (node (ref "SLAVE_MICRO_21") (pin "PD3") (pinfunction "PD3_PD3") (pintype "bidirectional"))
    )
    (net (code "429") (name "unconnected-(SLAVE_MICRO_21-PadPD4)") (class "Default")
      (node (ref "SLAVE_MICRO_21") (pin "PD4") (pinfunction "PD4_PD4") (pintype "bidirectional"))
    )
    (net (code "430") (name "unconnected-(SLAVE_MICRO_21-PadPD5)") (class "Default")
      (node (ref "SLAVE_MICRO_21") (pin "PD5") (pinfunction "PD5_PD5") (pintype "bidirectional"))
    )
    (net (code "431") (name "unconnected-(SLAVE_MICRO_22-PadANG)") (class "Default")
      (node (ref "SLAVE_MICRO_22") (pin "ANG") (pinfunction "ANG_ANG") (pintype "bidirectional"))
    )
    (net (code "432") (name "unconnected-(SLAVE_MICRO_22-PadPB0)") (class "Default")
      (node (ref "SLAVE_MICRO_22") (pin "PB0") (pinfunction "PB0_PB0") (pintype "bidirectional"))
    )
    (net (code "433") (name "unconnected-(SLAVE_MICRO_22-PadPC3)") (class "Default")
      (node (ref "SLAVE_MICRO_22") (pin "PC3") (pinfunction "PC3_PC3") (pintype "bidirectional"))
    )
    (net (code "434") (name "unconnected-(SLAVE_MICRO_22-PadPC4)") (class "Default")
      (node (ref "SLAVE_MICRO_22") (pin "PC4") (pinfunction "PC4_PC4") (pintype "bidirectional"))
    )
    (net (code "435") (name "unconnected-(SLAVE_MICRO_22-PadPC5)") (class "Default")
      (node (ref "SLAVE_MICRO_22") (pin "PC5") (pinfunction "PC5_PC5") (pintype "bidirectional"))
    )
    (net (code "436") (name "unconnected-(SLAVE_MICRO_22-PadPD2)") (class "Default")
      (node (ref "SLAVE_MICRO_22") (pin "PD2") (pinfunction "PD2_PD2") (pintype "bidirectional"))
    )
    (net (code "437") (name "unconnected-(SLAVE_MICRO_22-PadPD3)") (class "Default")
      (node (ref "SLAVE_MICRO_22") (pin "PD3") (pinfunction "PD3_PD3") (pintype "bidirectional"))
    )
    (net (code "438") (name "unconnected-(SLAVE_MICRO_22-PadPD4)") (class "Default")
      (node (ref "SLAVE_MICRO_22") (pin "PD4") (pinfunction "PD4_PD4") (pintype "bidirectional"))
    )
    (net (code "439") (name "unconnected-(SLAVE_MICRO_22-PadPD5)") (class "Default")
      (node (ref "SLAVE_MICRO_22") (pin "PD5") (pinfunction "PD5_PD5") (pintype "bidirectional"))
    )
    (net (code "440") (name "unconnected-(SLAVE_MICRO_23-PadANG)") (class "Default")
      (node (ref "SLAVE_MICRO_23") (pin "ANG") (pinfunction "ANG_ANG") (pintype "bidirectional"))
    )
    (net (code "441") (name "unconnected-(SLAVE_MICRO_23-PadPB0)") (class "Default")
      (node (ref "SLAVE_MICRO_23") (pin "PB0") (pinfunction "PB0_PB0") (pintype "bidirectional"))
    )
    (net (code "442") (name "unconnected-(SLAVE_MICRO_23-PadPC3)") (class "Default")
      (node (ref "SLAVE_MICRO_23") (pin "PC3") (pinfunction "PC3_PC3") (pintype "bidirectional"))
    )
    (net (code "443") (name "unconnected-(SLAVE_MICRO_23-PadPC4)") (class "Default")
      (node (ref "SLAVE_MICRO_23") (pin "PC4") (pinfunction "PC4_PC4") (pintype "bidirectional"))
    )
    (net (code "444") (name "unconnected-(SLAVE_MICRO_23-PadPC5)") (class "Default")
      (node (ref "SLAVE_MICRO_23") (pin "PC5") (pinfunction "PC5_PC5") (pintype "bidirectional"))
    )
    (net (code "445") (name "unconnected-(SLAVE_MICRO_23-PadPD2)") (class "Default")
      (node (ref "SLAVE_MICRO_23") (pin "PD2") (pinfunction "PD2_PD2") (pintype "bidirectional"))
    )
    (net (code "446") (name "unconnected-(SLAVE_MICRO_23-PadPD3)") (class "Default")
      (node (ref "SLAVE_MICRO_23") (pin "PD3") (pinfunction "PD3_PD3") (pintype "bidirectional"))
    )
    (net (code "447") (name "unconnected-(SLAVE_MICRO_23-PadPD4)") (class "Default")
      (node (ref "SLAVE_MICRO_23") (pin "PD4") (pinfunction "PD4_PD4") (pintype "bidirectional"))
    )
    (net (code "448") (name "unconnected-(SLAVE_MICRO_23-PadPD5)") (class "Default")
      (node (ref "SLAVE_MICRO_23") (pin "PD5") (pinfunction "PD5_PD5") (pintype "bidirectional"))
    )
    (net (code "449") (name "unconnected-(SLAVE_MICRO_24-PadANG)") (class "Default")
      (node (ref "SLAVE_MICRO_24") (pin "ANG") (pinfunction "ANG_ANG") (pintype "bidirectional"))
    )
    (net (code "450") (name "unconnected-(SLAVE_MICRO_24-PadPB0)") (class "Default")
      (node (ref "SLAVE_MICRO_24") (pin "PB0") (pinfunction "PB0_PB0") (pintype "bidirectional"))
    )
    (net (code "451") (name "unconnected-(SLAVE_MICRO_24-PadPC3)") (class "Default")
      (node (ref "SLAVE_MICRO_24") (pin "PC3") (pinfunction "PC3_PC3") (pintype "bidirectional"))
    )
    (net (code "452") (name "unconnected-(SLAVE_MICRO_24-PadPC4)") (class "Default")
      (node (ref "SLAVE_MICRO_24") (pin "PC4") (pinfunction "PC4_PC4") (pintype "bidirectional"))
    )
    (net (code "453") (name "unconnected-(SLAVE_MICRO_24-PadPC5)") (class "Default")
      (node (ref "SLAVE_MICRO_24") (pin "PC5") (pinfunction "PC5_PC5") (pintype "bidirectional"))
    )
    (net (code "454") (name "unconnected-(SLAVE_MICRO_24-PadPD2)") (class "Default")
      (node (ref "SLAVE_MICRO_24") (pin "PD2") (pinfunction "PD2_PD2") (pintype "bidirectional"))
    )
    (net (code "455") (name "unconnected-(SLAVE_MICRO_24-PadPD3)") (class "Default")
      (node (ref "SLAVE_MICRO_24") (pin "PD3") (pinfunction "PD3_PD3") (pintype "bidirectional"))
    )
    (net (code "456") (name "unconnected-(SLAVE_MICRO_24-PadPD4)") (class "Default")
      (node (ref "SLAVE_MICRO_24") (pin "PD4") (pinfunction "PD4_PD4") (pintype "bidirectional"))
    )
    (net (code "457") (name "unconnected-(SLAVE_MICRO_24-PadPD5)") (class "Default")
      (node (ref "SLAVE_MICRO_24") (pin "PD5") (pinfunction "PD5_PD5") (pintype "bidirectional"))
    )
    (net (code "458") (name "unconnected-(U$2-PadNC1)") (class "Default")
      (node (ref "U$2") (pin "NC1") (pinfunction "NC1_NC1") (pintype "no_connect"))
    )
    (net (code "459") (name "unconnected-(U$2-PadNC2)") (class "Default")
      (node (ref "U$2") (pin "NC2") (pinfunction "NC2_NC2") (pintype "no_connect"))
    )
    (net (code "460") (name "unconnected-(U$2-PadVALVE_OUT1)") (class "Default")
      (node (ref "U$2") (pin "VALVE_OUT1") (pinfunction "VALVE_OUT1_VALVE_OUT1") (pintype "bidirectional"))
    )
    (net (code "461") (name "unconnected-(U$2-PadVALVE_OUT2)") (class "Default")
      (node (ref "U$2") (pin "VALVE_OUT2") (pinfunction "VALVE_OUT2_VALVE_OUT2") (pintype "bidirectional"))
    )
    (net (code "462") (name "unconnected-(U$2-PadVALVE_OUT3)") (class "Default")
      (node (ref "U$2") (pin "VALVE_OUT3") (pinfunction "VALVE_OUT3_VALVE_OUT3") (pintype "bidirectional"))
    )
    (net (code "463") (name "unconnected-(U$2-PadVALVE_OUT4)") (class "Default")
      (node (ref "U$2") (pin "VALVE_OUT4") (pinfunction "VALVE_OUT4_VALVE_OUT4") (pintype "bidirectional"))
    )
    (net (code "464") (name "unconnected-(U$2-PadVALVE_OUT5)") (class "Default")
      (node (ref "U$2") (pin "VALVE_OUT5") (pinfunction "VALVE_OUT5_VALVE_OUT5") (pintype "bidirectional"))
    )
    (net (code "465") (name "unconnected-(U$2-PadVALVE_OUT6)") (class "Default")
      (node (ref "U$2") (pin "VALVE_OUT6") (pinfunction "VALVE_OUT6_VALVE_OUT6") (pintype "bidirectional"))
    )
    (net (code "466") (name "unconnected-(U$2-PadVALVE_OUT7)") (class "Default")
      (node (ref "U$2") (pin "VALVE_OUT7") (pinfunction "VALVE_OUT7_VALVE_OUT7") (pintype "bidirectional"))
    )
    (net (code "467") (name "unconnected-(U$2-PadVALVE_OUT8)") (class "Default")
      (node (ref "U$2") (pin "VALVE_OUT8") (pinfunction "VALVE_OUT8_VALVE_OUT8") (pintype "bidirectional"))
    )
    (net (code "468") (name "unconnected-(U$2-PadVALVE_OUT9)") (class "Default")
      (node (ref "U$2") (pin "VALVE_OUT9") (pinfunction "VALVE_OUT9_VALVE_OUT9") (pintype "bidirectional"))
    )
    (net (code "469") (name "unconnected-(U$2-PadVALVE_OUT10)") (class "Default")
      (node (ref "U$2") (pin "VALVE_OUT10") (pinfunction "VALVE_OUT10_VALVE_OUT10") (pintype "bidirectional"))
    )
    (net (code "470") (name "unconnected-(U$2-PadVALVE_OUT11)") (class "Default")
      (node (ref "U$2") (pin "VALVE_OUT11") (pinfunction "VALVE_OUT11_VALVE_OUT11") (pintype "bidirectional"))
    )
    (net (code "471") (name "unconnected-(U$2-PadVALVE_OUT12)") (class "Default")
      (node (ref "U$2") (pin "VALVE_OUT12") (pinfunction "VALVE_OUT12_VALVE_OUT12") (pintype "bidirectional"))
    )
    (net (code "472") (name "unconnected-(U$2-PadVALVE_OUT13)") (class "Default")
      (node (ref "U$2") (pin "VALVE_OUT13") (pinfunction "VALVE_OUT13_VALVE_OUT13") (pintype "bidirectional"))
    )
    (net (code "473") (name "unconnected-(U$2-PadVALVE_OUT14)") (class "Default")
      (node (ref "U$2") (pin "VALVE_OUT14") (pinfunction "VALVE_OUT14_VALVE_OUT14") (pintype "bidirectional"))
    )
    (net (code "474") (name "unconnected-(U$2-PadVALVE_OUT15)") (class "Default")
      (node (ref "U$2") (pin "VALVE_OUT15") (pinfunction "VALVE_OUT15_VALVE_OUT15") (pintype "bidirectional"))
    )
    (net (code "475") (name "unconnected-(U$2-PadVALVE_OUT16)") (class "Default")
      (node (ref "U$2") (pin "VALVE_OUT16") (pinfunction "VALVE_OUT16_VALVE_OUT16") (pintype "bidirectional"))
    )
    (net (code "476") (name "unconnected-(U$2-PadVALVE_OUT17)") (class "Default")
      (node (ref "U$2") (pin "VALVE_OUT17") (pinfunction "VALVE_OUT17_VALVE_OUT17") (pintype "bidirectional"))
    )
    (net (code "477") (name "unconnected-(U$2-PadVALVE_OUT18)") (class "Default")
      (node (ref "U$2") (pin "VALVE_OUT18") (pinfunction "VALVE_OUT18_VALVE_OUT18") (pintype "bidirectional"))
    )
    (net (code "478") (name "unconnected-(U$2-PadVALVE_OUT19)") (class "Default")
      (node (ref "U$2") (pin "VALVE_OUT19") (pinfunction "VALVE_OUT19_VALVE_OUT19") (pintype "bidirectional"))
    )
    (net (code "479") (name "unconnected-(U$2-PadVALVE_OUT20)") (class "Default")
      (node (ref "U$2") (pin "VALVE_OUT20") (pinfunction "VALVE_OUT20_VALVE_OUT20") (pintype "bidirectional"))
    )
    (net (code "480") (name "unconnected-(U$2-PadVALVE_OUT21)") (class "Default")
      (node (ref "U$2") (pin "VALVE_OUT21") (pinfunction "VALVE_OUT21_VALVE_OUT21") (pintype "bidirectional"))
    )
    (net (code "481") (name "unconnected-(U$2-PadVALVE_OUT22)") (class "Default")
      (node (ref "U$2") (pin "VALVE_OUT22") (pinfunction "VALVE_OUT22_VALVE_OUT22") (pintype "bidirectional"))
    )
    (net (code "482") (name "unconnected-(U$2-PadVALVE_OUT23)") (class "Default")
      (node (ref "U$2") (pin "VALVE_OUT23") (pinfunction "VALVE_OUT23_VALVE_OUT23") (pintype "bidirectional"))
    )
    (net (code "483") (name "unconnected-(U$2-PadVALVE_OUT24)") (class "Default")
      (node (ref "U$2") (pin "VALVE_OUT24") (pinfunction "VALVE_OUT24_VALVE_OUT24") (pintype "bidirectional"))
    )
  )
)
